# hand_bot.net
KiCad netlist of a schematic drawn in Altium Designer
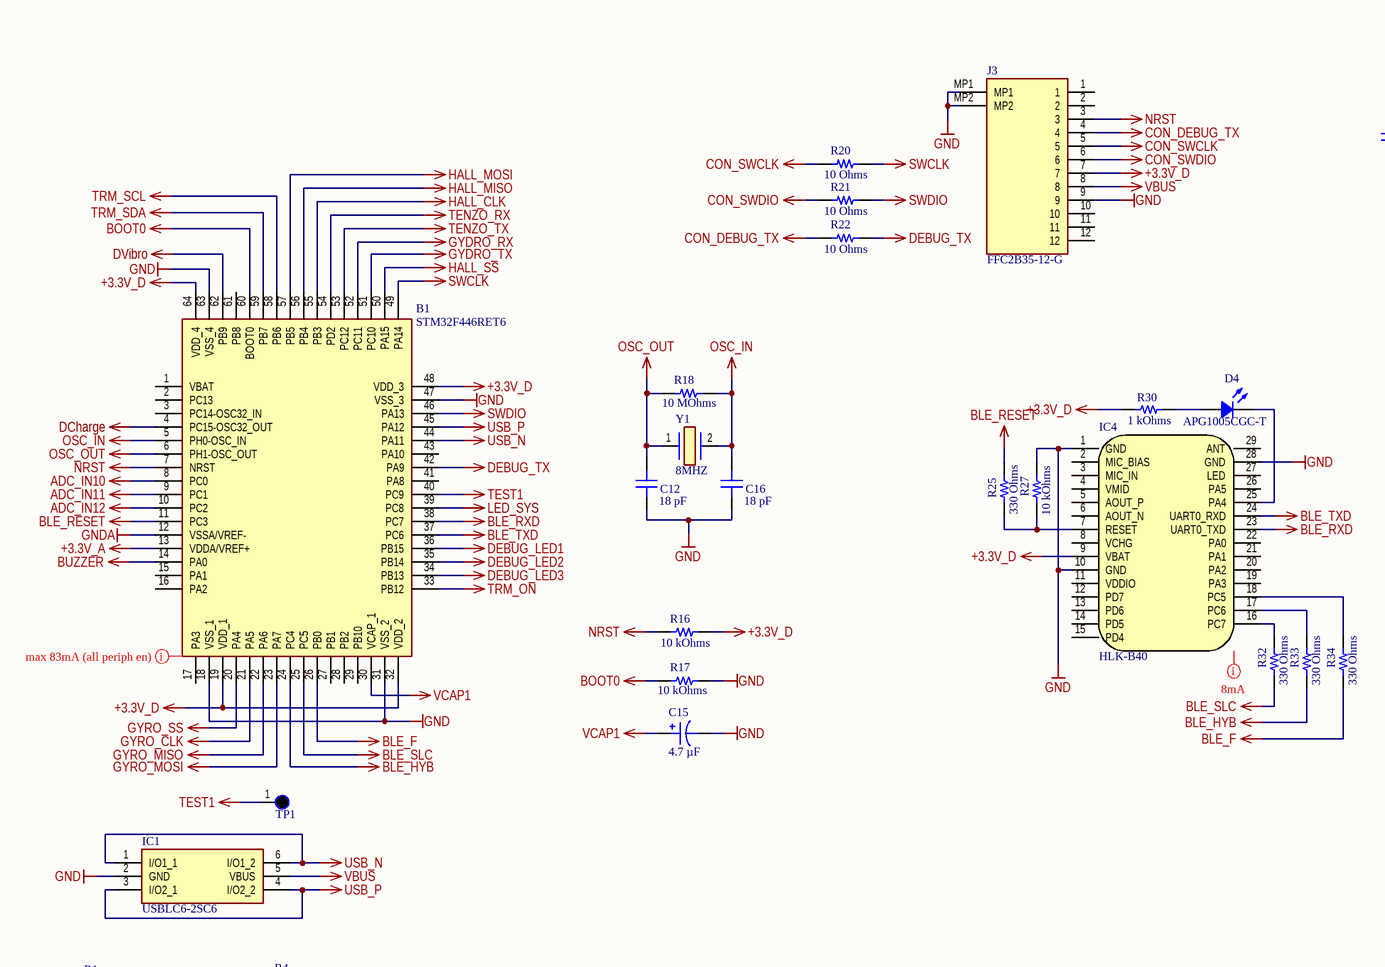
[diagram p0: hand_bot.SchDoc, top left]
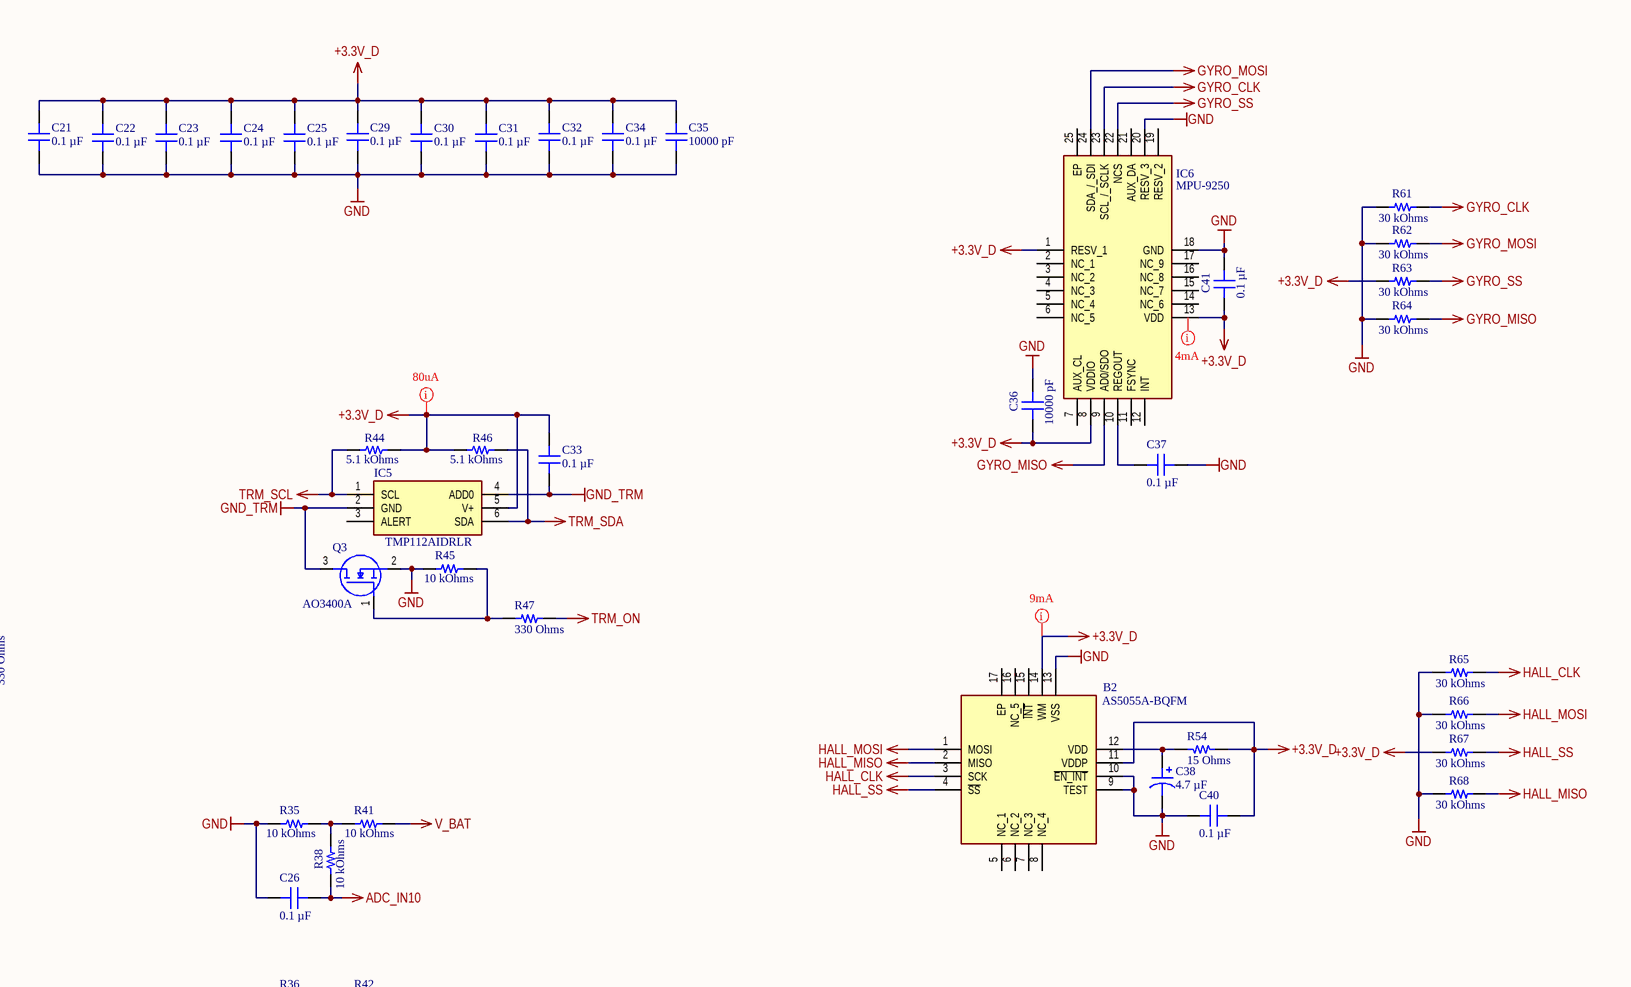
[diagram p1: hand_bot.SchDoc, top right]
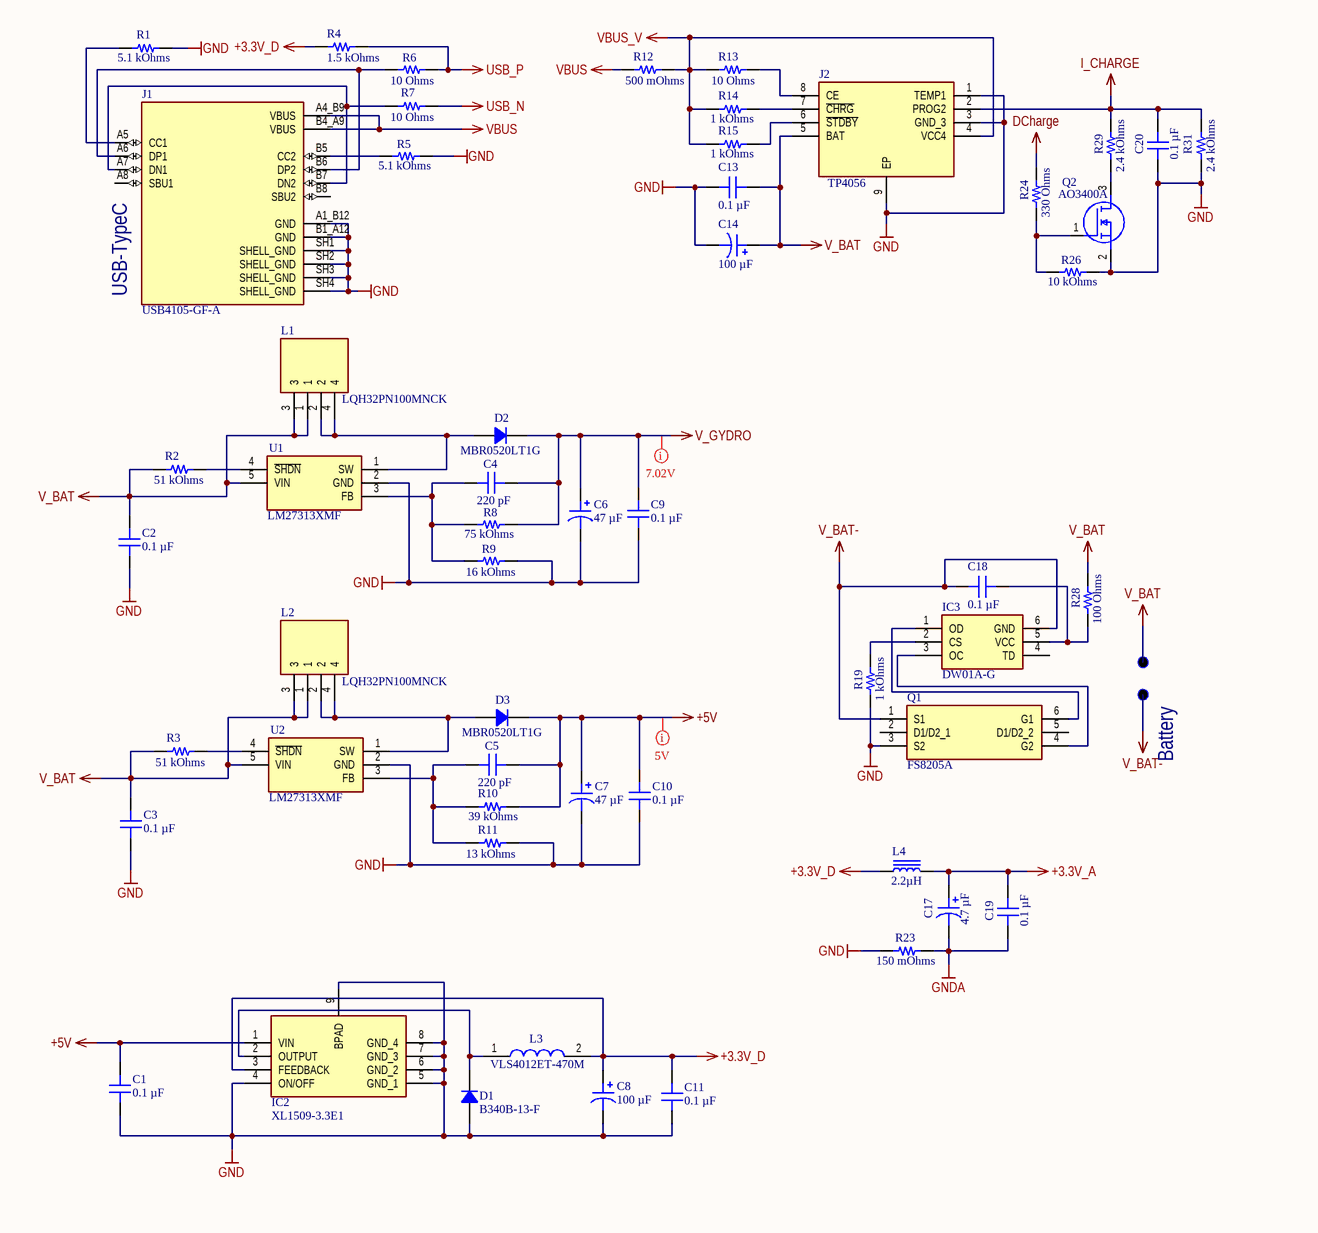
[diagram p2: hand_bot.SchDoc, bottom left]
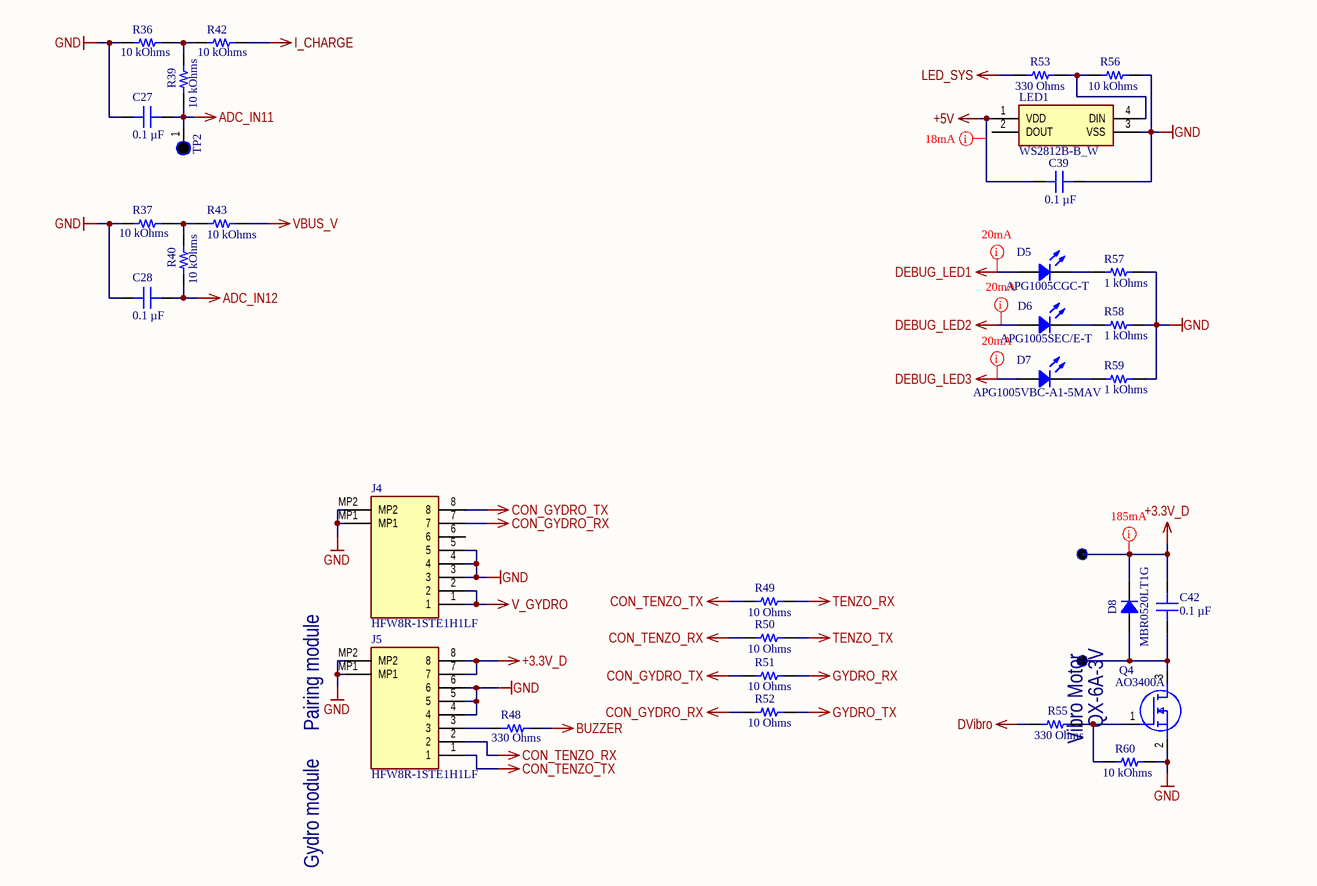
[diagram p3: hand_bot.SchDoc, bottom right]

(export (version "E")
  (design (tool "Eeschema 10.0.6"))
  (components
    (comp (ref "B1")
      (value "STM32F446RET6")
      (footprint "SamacSys:QFP50P1200X1200X160-64N")
      (description "Integrated Circuit")
      (fields (field (name "MOUSER PART NUMBER") "511-STM32F446RET6"))
      (libsource (lib "*") (part "STM32F446RET6"))
    )
    (comp (ref "B2")
      (value "AS5055A-BQFM")
      (footprint "SamacSys:QFN65P400X400X100-17N-D")
      (description "Integrated Circuit")
      (fields (field (name "MOUSER PART NUMBER") "985-AS5055A-BQFM"))
      (libsource (lib "SamacSys") (part "AS5055A-BQFM"))
    )
    (comp (ref "C1")
      (value "0.1 µF")
      (footprint "CAP 0402_1005")
      (description "CAP CER 0.1UF 50V X7R 0402")
      (fields (field (name "PART NUMBER") "CC0402KRX7R9BB104") (field (name "MANUFACTURER") "Yageo"))
      (libsource (lib "Celestial Altium Library - altium_library") (part "Capacitor"))
    )
    (comp (ref "C2")
      (value "0.1 µF")
      (footprint "CAP 0402_1005")
      (description "CAP CER 0.1UF 50V X7R 0402")
      (fields (field (name "PART NUMBER") "CC0402KRX7R9BB104") (field (name "MANUFACTURER") "Yageo"))
      (libsource (lib "Celestial Altium Library - altium_library") (part "Capacitor"))
    )
    (comp (ref "C3")
      (value "0.1 µF")
      (footprint "CAP 0402_1005")
      (description "CAP CER 0.1UF 50V X7R 0402")
      (fields (field (name "PART NUMBER") "CC0402KRX7R9BB104") (field (name "MANUFACTURER") "Yageo"))
      (libsource (lib "Celestial Altium Library - altium_library") (part "Capacitor"))
    )
    (comp (ref "C4")
      (value "220 pF")
      (footprint "CAP 0402_1005")
      (description "CAP CER 220PF 50V X7R 0402")
      (fields (field (name "PART NUMBER") "CC0402JRX7R9BB221") (field (name "MANUFACTURER") "Yageo"))
      (libsource (lib "Celestial Altium Library - altium_library") (part "Capacitor"))
    )
    (comp (ref "C5")
      (value "220 pF")
      (footprint "CAP 0402_1005")
      (description "CAP CER 220PF 50V X7R 0402")
      (fields (field (name "PART NUMBER") "CC0402JRX7R9BB221") (field (name "MANUFACTURER") "Yageo"))
      (libsource (lib "Celestial Altium Library - altium_library") (part "Capacitor"))
    )
    (comp (ref "C6")
      (value "47 µF")
      (footprint "CAP POL 1411_3528")
      (description "CAP TANT 47UF 20% 16V 1411")
      (fields (field (name "PART NUMBER") "TMCMB1C476MTRF") (field (name "MANUFACTURER") "Vishay Sprague"))
      (libsource (lib "Celestial Altium Library - altium_library") (part "Polarised Capacitor"))
    )
    (comp (ref "C7")
      (value "47 µF")
      (footprint "CAP POL 1411_3528")
      (description "CAP TANT 47UF 20% 16V 1411")
      (fields (field (name "PART NUMBER") "TMCMB1C476MTRF") (field (name "MANUFACTURER") "Vishay Sprague"))
      (libsource (lib "Celestial Altium Library - altium_library") (part "Polarised Capacitor"))
    )
    (comp (ref "C8")
      (value "100 µF")
      (footprint "CAP POL 1411_3528")
      (description "CAP TANT 100UF 20% 10V 1411")
      (fields (field (name "PART NUMBER") "T495B107M010ATE500") (field (name "MANUFACTURER") "KEMET"))
      (libsource (lib "Celestial Altium Library - altium_library") (part "Polarised Capacitor"))
    )
    (comp (ref "C9")
      (value "0.1 µF")
      (footprint "CAP 0402_1005")
      (description "CAP CER 0.1UF 50V X7R 0402")
      (fields (field (name "PART NUMBER") "CC0402KRX7R9BB104") (field (name "MANUFACTURER") "Yageo"))
      (libsource (lib "Celestial Altium Library - altium_library") (part "Capacitor"))
    )
    (comp (ref "C10")
      (value "0.1 µF")
      (footprint "CAP 0402_1005")
      (description "CAP CER 0.1UF 50V X7R 0402")
      (fields (field (name "PART NUMBER") "CC0402KRX7R9BB104") (field (name "MANUFACTURER") "Yageo"))
      (libsource (lib "Celestial Altium Library - altium_library") (part "Capacitor"))
    )
    (comp (ref "C11")
      (value "0.1 µF")
      (footprint "CAP 0402_1005")
      (description "CAP CER 0.1UF 50V X7R 0402")
      (fields (field (name "PART NUMBER") "CC0402KRX7R9BB104") (field (name "MANUFACTURER") "Yageo"))
      (libsource (lib "Celestial Altium Library - altium_library") (part "Capacitor"))
    )
    (comp (ref "C12")
      (value "18 pF")
      (footprint "CAP 0402_1005")
      (description "CAP CER 18PF 50V C0G/NPO 0402")
      (fields (field (name "PART NUMBER") "CC0402FRNPO9BN180") (field (name "MANUFACTURER") "Yageo"))
      (libsource (lib "Celestial Altium Library - altium_library") (part "Capacitor"))
    )
    (comp (ref "C13")
      (value "0.1 µF")
      (footprint "CAP 0402_1005")
      (description "CAP CER 0.1UF 50V X7R 0402")
      (fields (field (name "PART NUMBER") "CC0402KRX7R9BB104") (field (name "MANUFACTURER") "Yageo"))
      (libsource (lib "Celestial Altium Library - altium_library") (part "Capacitor"))
    )
    (comp (ref "C14")
      (value "100 µF")
      (footprint "CAP POL 1411_3528")
      (description "CAP TANT 100UF 20% 10V 1411")
      (fields (field (name "PART NUMBER") "T495B107M010ATE500") (field (name "MANUFACTURER") "KEMET"))
      (libsource (lib "") (part "Polarised Capacitor_1"))
    )
    (comp (ref "C15")
      (value "4.7 µF")
      (footprint "CAP POL 1206_3216")
      (description "CAP TANT 4.7UF 20% 16V 1206")
      (fields (field (name "PART NUMBER") "T491A475M016AT") (field (name "MANUFACTURER") "KEMET"))
      (libsource (lib "") (part "Polarised Capacitor_1"))
    )
    (comp (ref "C16")
      (value "18 pF")
      (footprint "CAP 0402_1005")
      (description "CAP CER 18PF 50V C0G/NPO 0402")
      (fields (field (name "PART NUMBER") "CC0402FRNPO9BN180") (field (name "MANUFACTURER") "Yageo"))
      (libsource (lib "Celestial Altium Library - altium_library") (part "Capacitor"))
    )
    (comp (ref "C17")
      (value "4.7 µF")
      (footprint "CAP POL 1206_3216")
      (description "CAP TANT 4.7UF 20% 16V 1206")
      (fields (field (name "PART NUMBER") "T491A475M016AT") (field (name "MANUFACTURER") "KEMET"))
      (libsource (lib "Celestial Altium Library - altium_library") (part "Polarised Capacitor"))
    )
    (comp (ref "C18")
      (value "0.1 µF")
      (footprint "CAP 0402_1005")
      (description "CAP CER 0.1UF 50V X7R 0402")
      (fields (field (name "PART NUMBER") "CC0402KRX7R9BB104") (field (name "MANUFACTURER") "Yageo"))
      (libsource (lib "Celestial Altium Library - altium_library") (part "Capacitor"))
    )
    (comp (ref "C19")
      (value "0.1 µF")
      (footprint "CAP 0402_1005")
      (description "CAP CER 0.1UF 50V X7R 0402")
      (fields (field (name "PART NUMBER") "CC0402KRX7R9BB104") (field (name "MANUFACTURER") "Yageo"))
      (libsource (lib "Celestial Altium Library - altium_library") (part "Capacitor"))
    )
    (comp (ref "C20")
      (value "0.1 µF")
      (footprint "CAP 0402_1005")
      (description "CAP CER 0.1UF 50V X7R 0402")
      (fields (field (name "PART NUMBER") "CC0402KRX7R9BB104") (field (name "MANUFACTURER") "Yageo"))
      (libsource (lib "Celestial Altium Library - altium_library") (part "Capacitor"))
    )
    (comp (ref "C21")
      (value "0.1 µF")
      (footprint "CAP 0402_1005")
      (description "CAP CER 0.1UF 50V X7R 0402")
      (fields (field (name "PART NUMBER") "CC0402KRX7R9BB104") (field (name "MANUFACTURER") "Yageo"))
      (libsource (lib "Celestial Altium Library - altium_library") (part "Capacitor"))
    )
    (comp (ref "C22")
      (value "0.1 µF")
      (footprint "CAP 0402_1005")
      (description "CAP CER 0.1UF 50V X7R 0402")
      (fields (field (name "PART NUMBER") "CC0402KRX7R9BB104") (field (name "MANUFACTURER") "Yageo"))
      (libsource (lib "Celestial Altium Library - altium_library") (part "Capacitor"))
    )
    (comp (ref "C23")
      (value "0.1 µF")
      (footprint "CAP 0402_1005")
      (description "CAP CER 0.1UF 50V X7R 0402")
      (fields (field (name "PART NUMBER") "CC0402KRX7R9BB104") (field (name "MANUFACTURER") "Yageo"))
      (libsource (lib "Celestial Altium Library - altium_library") (part "Capacitor"))
    )
    (comp (ref "C24")
      (value "0.1 µF")
      (footprint "CAP 0402_1005")
      (description "CAP CER 0.1UF 50V X7R 0402")
      (fields (field (name "PART NUMBER") "CC0402KRX7R9BB104") (field (name "MANUFACTURER") "Yageo"))
      (libsource (lib "Celestial Altium Library - altium_library") (part "Capacitor"))
    )
    (comp (ref "C25")
      (value "0.1 µF")
      (footprint "CAP 0402_1005")
      (description "CAP CER 0.1UF 50V X7R 0402")
      (fields (field (name "PART NUMBER") "CC0402KRX7R9BB104") (field (name "MANUFACTURER") "Yageo"))
      (libsource (lib "Celestial Altium Library - altium_library") (part "Capacitor"))
    )
    (comp (ref "C26")
      (value "0.1 µF")
      (footprint "CAP 0402_1005")
      (description "CAP CER 0.1UF 50V X7R 0402")
      (fields (field (name "PART NUMBER") "CC0402KRX7R9BB104") (field (name "MANUFACTURER") "Yageo"))
      (libsource (lib "Celestial Altium Library - altium_library") (part "Capacitor"))
    )
    (comp (ref "C27")
      (value "0.1 µF")
      (footprint "CAP 0402_1005")
      (description "CAP CER 0.1UF 50V X7R 0402")
      (fields (field (name "PART NUMBER") "CC0402KRX7R9BB104") (field (name "MANUFACTURER") "Yageo"))
      (libsource (lib "Celestial Altium Library - altium_library") (part "Capacitor"))
    )
    (comp (ref "C28")
      (value "0.1 µF")
      (footprint "CAP 0402_1005")
      (description "CAP CER 0.1UF 50V X7R 0402")
      (fields (field (name "PART NUMBER") "CC0402KRX7R9BB104") (field (name "MANUFACTURER") "Yageo"))
      (libsource (lib "Celestial Altium Library - altium_library") (part "Capacitor"))
    )
    (comp (ref "C29")
      (value "0.1 µF")
      (footprint "CAP 0402_1005")
      (description "CAP CER 0.1UF 50V X7R 0402")
      (fields (field (name "PART NUMBER") "CC0402KRX7R9BB104") (field (name "MANUFACTURER") "Yageo"))
      (libsource (lib "Celestial Altium Library - altium_library") (part "Capacitor"))
    )
    (comp (ref "C30")
      (value "0.1 µF")
      (footprint "CAP 0402_1005")
      (description "CAP CER 0.1UF 50V X7R 0402")
      (fields (field (name "PART NUMBER") "CC0402KRX7R9BB104") (field (name "MANUFACTURER") "Yageo"))
      (libsource (lib "Celestial Altium Library - altium_library") (part "Capacitor"))
    )
    (comp (ref "C31")
      (value "0.1 µF")
      (footprint "CAP 0402_1005")
      (description "CAP CER 0.1UF 50V X7R 0402")
      (fields (field (name "PART NUMBER") "CC0402KRX7R9BB104") (field (name "MANUFACTURER") "Yageo"))
      (libsource (lib "Celestial Altium Library - altium_library") (part "Capacitor"))
    )
    (comp (ref "C32")
      (value "0.1 µF")
      (footprint "CAP 0402_1005")
      (description "CAP CER 0.1UF 50V X7R 0402")
      (fields (field (name "PART NUMBER") "CC0402KRX7R9BB104") (field (name "MANUFACTURER") "Yageo"))
      (libsource (lib "Celestial Altium Library - altium_library") (part "Capacitor"))
    )
    (comp (ref "C33")
      (value "0.1 µF")
      (footprint "CAP 0402_1005")
      (description "CAP CER 0.1UF 50V X7R 0402")
      (fields (field (name "PART NUMBER") "CC0402KRX7R9BB104") (field (name "MANUFACTURER") "Yageo"))
      (libsource (lib "Celestial Altium Library - altium_library") (part "Capacitor"))
    )
    (comp (ref "C34")
      (value "0.1 µF")
      (footprint "CAP 0402_1005")
      (description "CAP CER 0.1UF 50V X7R 0402")
      (fields (field (name "PART NUMBER") "CC0402KRX7R9BB104") (field (name "MANUFACTURER") "Yageo"))
      (libsource (lib "Celestial Altium Library - altium_library") (part "Capacitor"))
    )
    (comp (ref "C35")
      (value "10000 pF")
      (footprint "CAP 0402_1005")
      (description "CAP CER 10000PF 50V X7R 0402")
      (fields (field (name "PART NUMBER") "CC0402KRX7R9BB103") (field (name "MANUFACTURER") "Yageo"))
      (libsource (lib "Celestial Altium Library - altium_library") (part "Capacitor"))
    )
    (comp (ref "C36")
      (value "10000 pF")
      (footprint "CAP 0402_1005")
      (description "CAP CER 10000PF 50V X7R 0402")
      (fields (field (name "PART NUMBER") "CC0402KRX7R9BB103") (field (name "MANUFACTURER") "Yageo"))
      (libsource (lib "Celestial Altium Library - altium_library") (part "Capacitor"))
    )
    (comp (ref "C37")
      (value "0.1 µF")
      (footprint "CAP 0402_1005")
      (description "CAP CER 0.1UF 50V X7R 0402")
      (fields (field (name "PART NUMBER") "CC0402KRX7R9BB104") (field (name "MANUFACTURER") "Yageo"))
      (libsource (lib "Celestial Altium Library - altium_library") (part "Capacitor"))
    )
    (comp (ref "C38")
      (value "4.7 µF")
      (footprint "CAP POL 1206_3216")
      (description "CAP TANT 4.7UF 20% 16V 1206")
      (fields (field (name "PART NUMBER") "T491A475M016AT") (field (name "MANUFACTURER") "KEMET"))
      (libsource (lib "Celestial Altium Library - altium_library") (part "Polarised Capacitor"))
    )
    (comp (ref "C39")
      (value "0.1 µF")
      (footprint "CAP 0402_1005")
      (description "CAP CER 0.1UF 50V X7R 0402")
      (fields (field (name "PART NUMBER") "CC0402KRX7R9BB104") (field (name "MANUFACTURER") "Yageo"))
      (libsource (lib "Celestial Altium Library - altium_library") (part "Capacitor"))
    )
    (comp (ref "C40")
      (value "0.1 µF")
      (footprint "CAP 0402_1005")
      (description "CAP CER 0.1UF 50V X7R 0402")
      (fields (field (name "PART NUMBER") "CC0402KRX7R9BB104") (field (name "MANUFACTURER") "Yageo"))
      (libsource (lib "Celestial Altium Library - altium_library") (part "Capacitor"))
    )
    (comp (ref "C41")
      (value "0.1 µF")
      (footprint "CAP 0402_1005")
      (description "CAP CER 0.1UF 50V X7R 0402")
      (fields (field (name "PART NUMBER") "CC0402KRX7R9BB104") (field (name "MANUFACTURER") "Yageo"))
      (libsource (lib "Celestial Altium Library - altium_library") (part "Capacitor"))
    )
    (comp (ref "C42")
      (value "0.1 µF")
      (footprint "CAP 0402_1005")
      (description "CAP CER 0.1UF 50V X7R 0402")
      (fields (field (name "PART NUMBER") "CC0402KRX7R9BB104") (field (name "MANUFACTURER") "Yageo"))
      (libsource (lib "Celestial Altium Library - altium_library") (part "Capacitor"))
    )
    (comp (ref "D1")
      (value "B340B-13-F")
      (footprint "DO214AA SMB")
      (description "DIODE SCHOTTKY 40V 3A SMB")
      (fields (field (name "MANUFACTURER") "Diodes Incorporated"))
      (libsource (lib "Celestial Altium Library - altium_library") (part "Diode"))
    )
    (comp (ref "D2")
      (value "MBR0520LT1G")
      (footprint "SOD-123")
      (description "DIODE SCHOTTKY 20V 500MA SOD123")
      (fields (field (name "MANUFACTURER") "ON Semiconductor"))
      (libsource (lib "Celestial Altium Library - altium_library") (part "Diode"))
    )
    (comp (ref "D3")
      (value "MBR0520LT1G")
      (footprint "SOD-123")
      (description "DIODE SCHOTTKY 20V 500MA SOD123")
      (fields (field (name "MANUFACTURER") "ON Semiconductor"))
      (libsource (lib "Celestial Altium Library - altium_library") (part "Diode"))
    )
    (comp (ref "D4")
      (value "APG1005CGC-T")
      (footprint "LED 0402_1005 GREEN")
      (description "LED GREEN CLEAR CHIP SMD")
      (fields (field (name "MANUFACTURER") "Kingbright"))
      (libsource (lib "Celestial Altium Library - altium_library") (part "LED"))
    )
    (comp (ref "D5")
      (value "APG1005CGC-T")
      (footprint "LED 0402_1005 GREEN")
      (description "LED GREEN CLEAR CHIP SMD")
      (fields (field (name "MANUFACTURER") "Kingbright"))
      (libsource (lib "Celestial Altium Library - altium_library") (part "LED"))
    )
    (comp (ref "D6")
      (value "Red")
      (footprint "LED 0402_1005 RED")
      (description "LED RED CLEAR CHIP SMD")
      (fields (field (name "PART NUMBER") "APG1005SEC/E-T") (field (name "MANUFACTURER") "Kingbright"))
      (libsource (lib "Celestial Altium Library - altium_library") (part "LED"))
    )
    (comp (ref "D7")
      (value "Blue")
      (footprint "LED 0402_1005 BLUE")
      (description "LED BLUE CLEAR 0402 SMD")
      (fields (field (name "PART NUMBER") "APG1005VBC-A1-5MAV") (field (name "MANUFACTURER") "Kingbright"))
      (libsource (lib "Celestial Altium Library - altium_library") (part "LED"))
    )
    (comp (ref "D8")
      (value "MBR0520LT1G")
      (footprint "SOD-123")
      (description "DIODE SCHOTTKY 20V 500MA SOD123")
      (fields (field (name "MANUFACTURER") "ON Semiconductor"))
      (libsource (lib "Celestial Altium Library - altium_library") (part "Diode"))
    )
    (comp (ref "IC1")
      (value "USBLC6-2SC6")
      (footprint "SamacSys:SOT95P280X145-6N")
      (description "Integrated Circuit")
      (fields (field (name "MOUSER PART NUMBER") "511-USBLC6-2SC6"))
      (libsource (lib "*") (part "USBLC6-2SC6"))
    )
    (comp (ref "IC2")
      (value "XL1509-3.3E1")
      (footprint "SamacSys:SOIC127P600X175-8N_BPAD")
      (description "Integrated Circuit")
      (libsource (lib "SamacSys") (part "XL1509-3.3E1"))
    )
    (comp (ref "IC3")
      (value "DW01A-G")
      (footprint "SamacSys:SOT95P280X135-6N")
      (description "Integrated Circuit")
      (libsource (lib "*") (part "DW01A-G"))
    )
    (comp (ref "IC4")
      (value "HLK-B40")
      (footprint "hlk-b40")
      (fields (field (name "MANUFACTURER") "HI-LINK(海凌科)"))
      (libsource (lib "SamacSys") (part "HLK-B40"))
    )
    (comp (ref "IC5")
      (value "TMP112AIDRLR")
      (footprint "SamacSys:SOTFL50P160X60-6N")
      (description "Integrated Circuit")
      (fields (field (name "MANUFACTURER_PART_NUMBER") "TMP112AIDRLR-869127202"))
      (libsource (lib "*") (part "TMP112AIDRLR-869127202"))
    )
    (comp (ref "IC6")
      (value "MPU-9250")
      (footprint "SamacSys:QFN40P300X300X105-25N-D")
      (description "Integrated Circuit")
      (fields (field (name "MANUFACTURER_PART_NUMBER") "InvenSense MPU-9250"))
      (libsource (lib "*") (part "InvenSense_MPU-9250"))
    )
    (comp (ref "J1")
      (value "USB4105-GF-A")
      (footprint "GCT_USB4105-GF-A")
      (fields (field (name "MF") "GCT"))
      (libsource (lib "USB4105-GF-A") (part "USB4105-GF-A"))
    )
    (comp (ref "J2")
      (value "TP4056")
      (footprint "SamacSys:SOIC127P600X175-9N")
      (description "Connector")
      (libsource (lib "*") (part "TP4056"))
    )
    (comp (ref "J3")
      (value "FFC2B35-12-G")
      (footprint "SamacSys:FFC2B3512G")
      (description "Connector")
      (fields (field (name "MOUSER PART NUMBER") "640-FFC2B35-12-G"))
      (libsource (lib "*") (part "FFC2B35-12-G"))
    )
    (comp (ref "J4")
      (value "HFW8R-1STE1H1LF")
      (footprint "SamacSys:HFW8R1STE1H1LF")
      (description "Connector")
      (fields (field (name "MOUSER PART NUMBER") "649-HFW8R-1STE1H1LF"))
      (libsource (lib "SamacSys") (part "HFW8R-1STE1H1LF"))
    )
    (comp (ref "J5")
      (value "HFW8R-1STE1H1LF")
      (footprint "SamacSys:HFW8R1STE1H1LF")
      (description "Connector")
      (fields (field (name "MOUSER PART NUMBER") "649-HFW8R-1STE1H1LF"))
      (libsource (lib "SamacSys") (part "HFW8R-1STE1H1LF"))
    )
    (comp (ref "L1")
      (value "LQH32PN100MNCK")
      (footprint "SamacSys:LQH32CH100K53L")
      (description "Inductor")
      (libsource (lib "*") (part "LQH32PN100MNCK"))
    )
    (comp (ref "L2")
      (value "LQH32PN100MNCK")
      (footprint "SamacSys:LQH32CH100K53L")
      (description "Inductor")
      (libsource (lib "*") (part "LQH32PN100MNCK"))
    )
    (comp (ref "L3")
      (value "VLS4012ET-470M")
      (footprint "SamacSys:VLS4012")
      (description "Inductor")
      (fields (field (name "MOUSER PART NUMBER") "810-VLS4012ET-470M"))
      (libsource (lib "*") (part "VLS4012ET-470M"))
    )
    (comp (ref "L4")
      (value "2.2µH")
      (footprint "IND 0603_1608 RF WW")
      (description "FIXED IND 2.2UH 750MA 345 MOHM")
      (fields (field (name "PART NUMBER") "MBKK1608T2R2M") (field (name "MANUFACTURER") "Taiyo Yuden"))
      (libsource (lib "Celestial Altium Library - altium_library") (part "Inductor"))
    )
    (comp (ref "LED1")
      (value "WS2812B-B_W")
      (footprint "SamacSys:WS2812BBW")
      (description "LED")
      (fields (field (name "MANUFACTURER_PART_NUMBER") "WS2812B-B/W"))
      (libsource (lib "*") (part "WS2812B-B_W"))
    )
    (comp (ref "Q1")
      (value "FS8205A")
      (footprint "SamacSys:SOT95P280X125-6N")
      (description "MOSFET (N-Channel)")
      (libsource (lib "*") (part "FS8205A"))
    )
    (comp (ref "Q2")
      (value "AO3400A")
      (footprint "SamacSys:SOT95P280X125-3N")
      (description "MOSFET (N-Channel)")
      (libsource (lib "SamacSys") (part "AO3400A"))
    )
    (comp (ref "Q3")
      (value "AO3400A")
      (footprint "SamacSys:SOT95P280X125-3N")
      (description "MOSFET (N-Channel)")
      (libsource (lib "SamacSys") (part "AO3400A"))
    )
    (comp (ref "Q4")
      (value "AO3400A")
      (footprint "SamacSys:SOT95P280X125-3N")
      (description "MOSFET (N-Channel)")
      (libsource (lib "SamacSys") (part "AO3400A"))
    )
    (comp (ref "R1")
      (value "5.1 kOhms")
      (footprint "RES 0402_1005")
      (description "RES 5.1K OHM 1% 1/16W 0402")
      (fields
        (field (name "PART NUMBER") "RMCF0402FT5K10")
        (field (name "MANUFACTURER") "Stackpole Electronics Inc")
      )
      (libsource (lib "Celestial Altium Library - altium_library") (part "Resistor"))
    )
    (comp (ref "R2")
      (value "51 kOhms")
      (footprint "RES 0402_1005")
      (description "RES 51K OHM 1% 1/16W 0402")
      (fields (field (name "PART NUMBER") "RC0402FR-0751KL") (field (name "MANUFACTURER") "Yageo"))
      (libsource (lib "Celestial Altium Library - altium_library") (part "Resistor"))
    )
    (comp (ref "R3")
      (value "51 kOhms")
      (footprint "RES 0402_1005")
      (description "RES 51K OHM 1% 1/16W 0402")
      (fields (field (name "PART NUMBER") "RC0402FR-0751KL") (field (name "MANUFACTURER") "Yageo"))
      (libsource (lib "Celestial Altium Library - altium_library") (part "Resistor"))
    )
    (comp (ref "R4")
      (value "1.5 kOhms")
      (footprint "RES 0402_1005")
      (description "RES 1.5K OHM 1% 1/16W 0402")
      (fields (field (name "PART NUMBER") "RC0402FR-071K5L") (field (name "MANUFACTURER") "Yageo"))
      (libsource (lib "Celestial Altium Library - altium_library") (part "Resistor"))
    )
    (comp (ref "R5")
      (value "5.1 kOhms")
      (footprint "RES 0402_1005")
      (description "RES 5.1K OHM 1% 1/16W 0402")
      (fields
        (field (name "PART NUMBER") "RMCF0402FT5K10")
        (field (name "MANUFACTURER") "Stackpole Electronics Inc")
      )
      (libsource (lib "Celestial Altium Library - altium_library") (part "Resistor"))
    )
    (comp (ref "R6")
      (value "10 Ohms")
      (footprint "RES 0402_1005")
      (description "RES 10 OHM 1% 1/8W 0402")
      (fields (field (name "PART NUMBER") "RC0402FR-7W10RL") (field (name "MANUFACTURER") "Yageo"))
      (libsource (lib "Celestial Altium Library - altium_library") (part "Resistor"))
    )
    (comp (ref "R7")
      (value "10 Ohms")
      (footprint "RES 0402_1005")
      (description "RES 10 OHM 1% 1/8W 0402")
      (fields (field (name "PART NUMBER") "RC0402FR-7W10RL") (field (name "MANUFACTURER") "Yageo"))
      (libsource (lib "Celestial Altium Library - altium_library") (part "Resistor"))
    )
    (comp (ref "R8")
      (value "75 kOhms")
      (footprint "RES 0402_1005")
      (description "RES 75K OHM 1% 1/16W 0402")
      (fields (field (name "PART NUMBER") "RC0402FR-0775KL") (field (name "MANUFACTURER") "Yageo"))
      (libsource (lib "Celestial Altium Library - altium_library") (part "Resistor"))
    )
    (comp (ref "R9")
      (value "16 kOhms")
      (footprint "RES 0402_1005")
      (description "RES 16K OHM 1% 1/16W 0402")
      (fields (field (name "PART NUMBER") "RC0402FR-0716KL") (field (name "MANUFACTURER") "Yageo"))
      (libsource (lib "Celestial Altium Library - altium_library") (part "Resistor"))
    )
    (comp (ref "R10")
      (value "39 kOhms")
      (footprint "RES 0402_1005")
      (description "RES 39K OHM 1% 1/16W 0402")
      (fields (field (name "PART NUMBER") "RC0402FR-0739KL") (field (name "MANUFACTURER") "Yageo"))
      (libsource (lib "Celestial Altium Library - altium_library") (part "Resistor"))
    )
    (comp (ref "R11")
      (value "13 kOhms")
      (footprint "RES 0402_1005")
      (description "RES 13K OHM 1% 1/16W 0402")
      (fields (field (name "PART NUMBER") "RC0402FR-0713KL") (field (name "MANUFACTURER") "Yageo"))
      (libsource (lib "Celestial Altium Library - altium_library") (part "Resistor"))
    )
    (comp (ref "R12")
      (value "500 mOhms")
      (footprint "RES 2512_6432")
      (description "RES 0.5 OHM 1% 1W 2512")
      (fields (field (name "PART NUMBER") "RL2512FK-070R5L") (field (name "MANUFACTURER") "Yageo"))
      (libsource (lib "Celestial Altium Library - altium_library") (part "Resistor"))
    )
    (comp (ref "R13")
      (value "10 Ohms")
      (footprint "RES 0402_1005")
      (description "RES 10 OHM 1% 1/8W 0402")
      (fields (field (name "PART NUMBER") "RC0402FR-7W10RL") (field (name "MANUFACTURER") "Yageo"))
      (libsource (lib "Celestial Altium Library - altium_library") (part "Resistor"))
    )
    (comp (ref "R14")
      (value "1 kOhms")
      (footprint "RES 0402_1005")
      (description "RES SMD 1K OHM 1% 1/16W 0402")
      (fields (field (name "PART NUMBER") "CR0402-FX-1001GLF") (field (name "MANUFACTURER") "Bourns Inc."))
      (libsource (lib "Celestial Altium Library - altium_library") (part "Resistor"))
    )
    (comp (ref "R15")
      (value "1 kOhms")
      (footprint "RES 0402_1005")
      (description "RES SMD 1K OHM 1% 1/16W 0402")
      (fields (field (name "PART NUMBER") "CR0402-FX-1001GLF") (field (name "MANUFACTURER") "Bourns Inc."))
      (libsource (lib "Celestial Altium Library - altium_library") (part "Resistor"))
    )
    (comp (ref "R16")
      (value "10 kOhms")
      (footprint "RES 0402_1005")
      (description "RES 10K OHM 1% 1/16W 0402")
      (fields
        (field (name "PART NUMBER") "RMCF0402FT10K0")
        (field (name "MANUFACTURER") "Stackpole Electronics Inc")
      )
      (libsource (lib "Celestial Altium Library - altium_library") (part "Resistor"))
    )
    (comp (ref "R17")
      (value "10 kOhms")
      (footprint "RES 0402_1005")
      (description "RES 10K OHM 1% 1/16W 0402")
      (fields
        (field (name "PART NUMBER") "RMCF0402FT10K0")
        (field (name "MANUFACTURER") "Stackpole Electronics Inc")
      )
      (libsource (lib "Celestial Altium Library - altium_library") (part "Resistor"))
    )
    (comp (ref "R18")
      (value "10 MOhms")
      (footprint "RES 0402_1005")
      (description "RES 10M OHM 1% 1/16W 0402")
      (fields (field (name "PART NUMBER") "RC0402FR-0710ML") (field (name "MANUFACTURER") "Yageo"))
      (libsource (lib "Celestial Altium Library - altium_library") (part "Resistor"))
    )
    (comp (ref "R19")
      (value "1 kOhms")
      (footprint "RES 0402_1005")
      (description "RES SMD 1K OHM 1% 1/16W 0402")
      (fields (field (name "PART NUMBER") "CR0402-FX-1001GLF") (field (name "MANUFACTURER") "Bourns Inc."))
      (libsource (lib "Celestial Altium Library - altium_library") (part "Resistor"))
    )
    (comp (ref "R20")
      (value "10 Ohms")
      (footprint "RES 0402_1005")
      (description "RES 10 OHM 1% 1/8W 0402")
      (fields (field (name "PART NUMBER") "RC0402FR-7W10RL") (field (name "MANUFACTURER") "Yageo"))
      (libsource (lib "Celestial Altium Library - altium_library") (part "Resistor"))
    )
    (comp (ref "R21")
      (value "10 Ohms")
      (footprint "RES 0402_1005")
      (description "RES 10 OHM 1% 1/8W 0402")
      (fields (field (name "PART NUMBER") "RC0402FR-7W10RL") (field (name "MANUFACTURER") "Yageo"))
      (libsource (lib "Celestial Altium Library - altium_library") (part "Resistor"))
    )
    (comp (ref "R22")
      (value "10 Ohms")
      (footprint "RES 0402_1005")
      (description "RES 10 OHM 1% 1/8W 0402")
      (fields (field (name "PART NUMBER") "RC0402FR-7W10RL") (field (name "MANUFACTURER") "Yageo"))
      (libsource (lib "Celestial Altium Library - altium_library") (part "Resistor"))
    )
    (comp (ref "R23")
      (value "150 mOhms")
      (footprint "RES 0805_2012")
      (description "RES 0.15 OHM 1% 1/8W 0805")
      (fields (field (name "PART NUMBER") "RL0805FR-070R15L") (field (name "MANUFACTURER") "Yageo"))
      (libsource (lib "Celestial Altium Library - altium_library") (part "Resistor"))
    )
    (comp (ref "R24")
      (value "330 Ohms")
      (footprint "RES 0402_1005")
      (description "RES 330 OHM 1% 1/16W 0402")
      (fields
        (field (name "PART NUMBER") "RMCF0402FT330R")
        (field (name "MANUFACTURER") "Stackpole Electronics Inc")
      )
      (libsource (lib "Celestial Altium Library - altium_library") (part "Resistor"))
    )
    (comp (ref "R25")
      (value "330 Ohms")
      (footprint "RES 0402_1005")
      (description "RES 330 OHM 1% 1/16W 0402")
      (fields
        (field (name "PART NUMBER") "RMCF0402FT330R")
        (field (name "MANUFACTURER") "Stackpole Electronics Inc")
      )
      (libsource (lib "Celestial Altium Library - altium_library") (part "Resistor"))
    )
    (comp (ref "R26")
      (value "10 kOhms")
      (footprint "RES 0402_1005")
      (description "RES 10K OHM 1% 1/16W 0402")
      (fields
        (field (name "PART NUMBER") "RMCF0402FT10K0")
        (field (name "MANUFACTURER") "Stackpole Electronics Inc")
      )
      (libsource (lib "Celestial Altium Library - altium_library") (part "Resistor"))
    )
    (comp (ref "R27")
      (value "10 kOhms")
      (footprint "RES 0402_1005")
      (description "RES 10K OHM 1% 1/16W 0402")
      (fields
        (field (name "PART NUMBER") "RMCF0402FT10K0")
        (field (name "MANUFACTURER") "Stackpole Electronics Inc")
      )
      (libsource (lib "Celestial Altium Library - altium_library") (part "Resistor"))
    )
    (comp (ref "R28")
      (value "100 Ohms")
      (footprint "RES 0402_1005")
      (description "RES 100 OHM 1% 1/8W 0402")
      (fields
        (field (name "PART NUMBER") "CRGP0402F100R")
        (field (name "MANUFACTURER") "TE Connectivity Passive Product")
      )
      (libsource (lib "Celestial Altium Library - altium_library") (part "Resistor"))
    )
    (comp (ref "R29")
      (value "2.4 kOhms")
      (footprint "RES 0402_1005")
      (description "RES 2.4K OHM 1% 1/16W 0402")
      (fields (field (name "PART NUMBER") "RC0402FR-072K4L") (field (name "MANUFACTURER") "Yageo"))
      (libsource (lib "Celestial Altium Library - altium_library") (part "Resistor"))
    )
    (comp (ref "R30")
      (value "1 kOhms")
      (footprint "RES 0402_1005")
      (description "RES SMD 1K OHM 1% 1/16W 0402")
      (fields (field (name "PART NUMBER") "CR0402-FX-1001GLF") (field (name "MANUFACTURER") "Bourns Inc."))
      (libsource (lib "Celestial Altium Library - altium_library") (part "Resistor"))
    )
    (comp (ref "R31")
      (value "2.4 kOhms")
      (footprint "RES 0402_1005")
      (description "RES 2.4K OHM 1% 1/16W 0402")
      (fields (field (name "PART NUMBER") "RC0402FR-072K4L") (field (name "MANUFACTURER") "Yageo"))
      (libsource (lib "Celestial Altium Library - altium_library") (part "Resistor"))
    )
    (comp (ref "R32")
      (value "330 Ohms")
      (footprint "RES 0402_1005")
      (description "RES 330 OHM 1% 1/16W 0402")
      (fields
        (field (name "PART NUMBER") "RMCF0402FT330R")
        (field (name "MANUFACTURER") "Stackpole Electronics Inc")
      )
      (libsource (lib "Celestial Altium Library - altium_library") (part "Resistor"))
    )
    (comp (ref "R33")
      (value "330 Ohms")
      (footprint "RES 0402_1005")
      (description "RES 330 OHM 1% 1/16W 0402")
      (fields
        (field (name "PART NUMBER") "RMCF0402FT330R")
        (field (name "MANUFACTURER") "Stackpole Electronics Inc")
      )
      (libsource (lib "Celestial Altium Library - altium_library") (part "Resistor"))
    )
    (comp (ref "R34")
      (value "330 Ohms")
      (footprint "RES 0402_1005")
      (description "RES 330 OHM 1% 1/16W 0402")
      (fields
        (field (name "PART NUMBER") "RMCF0402FT330R")
        (field (name "MANUFACTURER") "Stackpole Electronics Inc")
      )
      (libsource (lib "Celestial Altium Library - altium_library") (part "Resistor"))
    )
    (comp (ref "R35")
      (value "10 kOhms")
      (footprint "RES 0402_1005")
      (description "RES 10K OHM 1% 1/16W 0402")
      (fields
        (field (name "PART NUMBER") "RMCF0402FT10K0")
        (field (name "MANUFACTURER") "Stackpole Electronics Inc")
      )
      (libsource (lib "Celestial Altium Library - altium_library") (part "Resistor"))
    )
    (comp (ref "R36")
      (value "10 kOhms")
      (footprint "RES 0402_1005")
      (description "RES 10K OHM 1% 1/16W 0402")
      (fields
        (field (name "PART NUMBER") "RMCF0402FT10K0")
        (field (name "MANUFACTURER") "Stackpole Electronics Inc")
      )
      (libsource (lib "Celestial Altium Library - altium_library") (part "Resistor"))
    )
    (comp (ref "R37")
      (value "10 kOhms")
      (footprint "RES 0402_1005")
      (description "RES 10K OHM 1% 1/16W 0402")
      (fields
        (field (name "PART NUMBER") "RMCF0402FT10K0")
        (field (name "MANUFACTURER") "Stackpole Electronics Inc")
      )
      (libsource (lib "Celestial Altium Library - altium_library") (part "Resistor"))
    )
    (comp (ref "R38")
      (value "10 kOhms")
      (footprint "RES 0402_1005")
      (description "RES 10K OHM 1% 1/16W 0402")
      (fields
        (field (name "PART NUMBER") "RMCF0402FT10K0")
        (field (name "MANUFACTURER") "Stackpole Electronics Inc")
      )
      (libsource (lib "Celestial Altium Library - altium_library") (part "Resistor"))
    )
    (comp (ref "R39")
      (value "10 kOhms")
      (footprint "RES 0402_1005")
      (description "RES 10K OHM 1% 1/16W 0402")
      (fields
        (field (name "PART NUMBER") "RMCF0402FT10K0")
        (field (name "MANUFACTURER") "Stackpole Electronics Inc")
      )
      (libsource (lib "Celestial Altium Library - altium_library") (part "Resistor"))
    )
    (comp (ref "R40")
      (value "10 kOhms")
      (footprint "RES 0402_1005")
      (description "RES 10K OHM 1% 1/16W 0402")
      (fields
        (field (name "PART NUMBER") "RMCF0402FT10K0")
        (field (name "MANUFACTURER") "Stackpole Electronics Inc")
      )
      (libsource (lib "Celestial Altium Library - altium_library") (part "Resistor"))
    )
    (comp (ref "R41")
      (value "10 kOhms")
      (footprint "RES 0402_1005")
      (description "RES 10K OHM 1% 1/16W 0402")
      (fields
        (field (name "PART NUMBER") "RMCF0402FT10K0")
        (field (name "MANUFACTURER") "Stackpole Electronics Inc")
      )
      (libsource (lib "Celestial Altium Library - altium_library") (part "Resistor"))
    )
    (comp (ref "R42")
      (value "10 kOhms")
      (footprint "RES 0402_1005")
      (description "RES 10K OHM 1% 1/16W 0402")
      (fields
        (field (name "PART NUMBER") "RMCF0402FT10K0")
        (field (name "MANUFACTURER") "Stackpole Electronics Inc")
      )
      (libsource (lib "Celestial Altium Library - altium_library") (part "Resistor"))
    )
    (comp (ref "R43")
      (value "10 kOhms")
      (footprint "RES 0402_1005")
      (description "RES 10K OHM 1% 1/16W 0402")
      (fields
        (field (name "PART NUMBER") "RMCF0402FT10K0")
        (field (name "MANUFACTURER") "Stackpole Electronics Inc")
      )
      (libsource (lib "Celestial Altium Library - altium_library") (part "Resistor"))
    )
    (comp (ref "R44")
      (value "5.1 kOhms")
      (footprint "RES 0402_1005")
      (description "RES 5.1K OHM 1% 1/16W 0402")
      (fields
        (field (name "PART NUMBER") "RMCF0402FT5K10")
        (field (name "MANUFACTURER") "Stackpole Electronics Inc")
      )
      (libsource (lib "Celestial Altium Library - altium_library") (part "Resistor"))
    )
    (comp (ref "R45")
      (value "10 kOhms")
      (footprint "RES 0402_1005")
      (description "RES 10K OHM 1% 1/16W 0402")
      (fields
        (field (name "PART NUMBER") "RMCF0402FT10K0")
        (field (name "MANUFACTURER") "Stackpole Electronics Inc")
      )
      (libsource (lib "Celestial Altium Library - altium_library") (part "Resistor"))
    )
    (comp (ref "R46")
      (value "5.1 kOhms")
      (footprint "RES 0402_1005")
      (description "RES 5.1K OHM 1% 1/16W 0402")
      (fields
        (field (name "PART NUMBER") "RMCF0402FT5K10")
        (field (name "MANUFACTURER") "Stackpole Electronics Inc")
      )
      (libsource (lib "Celestial Altium Library - altium_library") (part "Resistor"))
    )
    (comp (ref "R47")
      (value "330 Ohms")
      (footprint "RES 0402_1005")
      (description "RES 330 OHM 1% 1/16W 0402")
      (fields
        (field (name "PART NUMBER") "RMCF0402FT330R")
        (field (name "MANUFACTURER") "Stackpole Electronics Inc")
      )
      (libsource (lib "Celestial Altium Library - altium_library") (part "Resistor"))
    )
    (comp (ref "R48")
      (value "330 Ohms")
      (footprint "RES 0402_1005")
      (description "RES 330 OHM 1% 1/16W 0402")
      (fields
        (field (name "PART NUMBER") "RMCF0402FT330R")
        (field (name "MANUFACTURER") "Stackpole Electronics Inc")
      )
      (libsource (lib "Celestial Altium Library - altium_library") (part "Resistor"))
    )
    (comp (ref "R49")
      (value "10 Ohms")
      (footprint "RES 0402_1005")
      (description "RES 10 OHM 1% 1/8W 0402")
      (fields (field (name "PART NUMBER") "RC0402FR-7W10RL") (field (name "MANUFACTURER") "Yageo"))
      (libsource (lib "Celestial Altium Library - altium_library") (part "Resistor"))
    )
    (comp (ref "R50")
      (value "10 Ohms")
      (footprint "RES 0402_1005")
      (description "RES 10 OHM 1% 1/8W 0402")
      (fields (field (name "PART NUMBER") "RC0402FR-7W10RL") (field (name "MANUFACTURER") "Yageo"))
      (libsource (lib "Celestial Altium Library - altium_library") (part "Resistor"))
    )
    (comp (ref "R51")
      (value "10 Ohms")
      (footprint "RES 0402_1005")
      (description "RES 10 OHM 1% 1/8W 0402")
      (fields (field (name "PART NUMBER") "RC0402FR-7W10RL") (field (name "MANUFACTURER") "Yageo"))
      (libsource (lib "Celestial Altium Library - altium_library") (part "Resistor"))
    )
    (comp (ref "R52")
      (value "10 Ohms")
      (footprint "RES 0402_1005")
      (description "RES 10 OHM 1% 1/8W 0402")
      (fields (field (name "PART NUMBER") "RC0402FR-7W10RL") (field (name "MANUFACTURER") "Yageo"))
      (libsource (lib "Celestial Altium Library - altium_library") (part "Resistor"))
    )
    (comp (ref "R53")
      (value "330 Ohms")
      (footprint "RES 0402_1005")
      (description "RES 330 OHM 1% 1/16W 0402")
      (fields
        (field (name "PART NUMBER") "RMCF0402FT330R")
        (field (name "MANUFACTURER") "Stackpole Electronics Inc")
      )
      (libsource (lib "Celestial Altium Library - altium_library") (part "Resistor"))
    )
    (comp (ref "R54")
      (value "15 Ohms")
      (footprint "RES 0603_1608")
      (description "RES 15 OHM 5% 1/10W 0603")
      (fields (field (name "PART NUMBER") "RC0603JR-0715RL") (field (name "MANUFACTURER") "Yageo"))
      (libsource (lib "Celestial Altium Library - altium_library") (part "Resistor"))
    )
    (comp (ref "R55")
      (value "330 Ohms")
      (footprint "RES 0402_1005")
      (description "RES 330 OHM 1% 1/16W 0402")
      (fields
        (field (name "PART NUMBER") "RMCF0402FT330R")
        (field (name "MANUFACTURER") "Stackpole Electronics Inc")
      )
      (libsource (lib "Celestial Altium Library - altium_library") (part "Resistor"))
    )
    (comp (ref "R56")
      (value "10 kOhms")
      (footprint "RES 0402_1005")
      (description "RES 10K OHM 1% 1/16W 0402")
      (fields
        (field (name "PART NUMBER") "RMCF0402FT10K0")
        (field (name "MANUFACTURER") "Stackpole Electronics Inc")
      )
      (libsource (lib "Celestial Altium Library - altium_library") (part "Resistor"))
    )
    (comp (ref "R57")
      (value "1 kOhms")
      (footprint "RES 0402_1005")
      (description "RES SMD 1K OHM 1% 1/16W 0402")
      (fields (field (name "PART NUMBER") "CR0402-FX-1001GLF") (field (name "MANUFACTURER") "Bourns Inc."))
      (libsource (lib "Celestial Altium Library - altium_library") (part "Resistor"))
    )
    (comp (ref "R58")
      (value "1 kOhms")
      (footprint "RES 0402_1005")
      (description "RES SMD 1K OHM 1% 1/16W 0402")
      (fields (field (name "PART NUMBER") "CR0402-FX-1001GLF") (field (name "MANUFACTURER") "Bourns Inc."))
      (libsource (lib "Celestial Altium Library - altium_library") (part "Resistor"))
    )
    (comp (ref "R59")
      (value "1 kOhms")
      (footprint "RES 0402_1005")
      (description "RES SMD 1K OHM 1% 1/16W 0402")
      (fields (field (name "PART NUMBER") "CR0402-FX-1001GLF") (field (name "MANUFACTURER") "Bourns Inc."))
      (libsource (lib "Celestial Altium Library - altium_library") (part "Resistor"))
    )
    (comp (ref "R60")
      (value "10 kOhms")
      (footprint "RES 0402_1005")
      (description "RES 10K OHM 1% 1/16W 0402")
      (fields
        (field (name "PART NUMBER") "RMCF0402FT10K0")
        (field (name "MANUFACTURER") "Stackpole Electronics Inc")
      )
      (libsource (lib "Celestial Altium Library - altium_library") (part "Resistor"))
    )
    (comp (ref "R61")
      (value "30 kOhms")
      (footprint "RES 0402_1005")
      (description "RES 30K OHM 1% 1/16W 0402")
      (fields (field (name "PART NUMBER") "RC0402FR-0730KL") (field (name "MANUFACTURER") "Yageo"))
      (libsource (lib "Celestial Altium Library - altium_library") (part "Resistor"))
    )
    (comp (ref "R62")
      (value "30 kOhms")
      (footprint "RES 0402_1005")
      (description "RES 30K OHM 1% 1/16W 0402")
      (fields (field (name "PART NUMBER") "RC0402FR-0730KL") (field (name "MANUFACTURER") "Yageo"))
      (libsource (lib "Celestial Altium Library - altium_library") (part "Resistor"))
    )
    (comp (ref "R63")
      (value "30 kOhms")
      (footprint "RES 0402_1005")
      (description "RES 30K OHM 1% 1/16W 0402")
      (fields (field (name "PART NUMBER") "RC0402FR-0730KL") (field (name "MANUFACTURER") "Yageo"))
      (libsource (lib "Celestial Altium Library - altium_library") (part "Resistor"))
    )
    (comp (ref "R64")
      (value "30 kOhms")
      (footprint "RES 0402_1005")
      (description "RES 30K OHM 1% 1/16W 0402")
      (fields (field (name "PART NUMBER") "RC0402FR-0730KL") (field (name "MANUFACTURER") "Yageo"))
      (libsource (lib "Celestial Altium Library - altium_library") (part "Resistor"))
    )
    (comp (ref "R65")
      (value "30 kOhms")
      (footprint "RES 0402_1005")
      (description "RES 30K OHM 1% 1/16W 0402")
      (fields (field (name "PART NUMBER") "RC0402FR-0730KL") (field (name "MANUFACTURER") "Yageo"))
      (libsource (lib "Celestial Altium Library - altium_library") (part "Resistor"))
    )
    (comp (ref "R66")
      (value "30 kOhms")
      (footprint "RES 0402_1005")
      (description "RES 30K OHM 1% 1/16W 0402")
      (fields (field (name "PART NUMBER") "RC0402FR-0730KL") (field (name "MANUFACTURER") "Yageo"))
      (libsource (lib "Celestial Altium Library - altium_library") (part "Resistor"))
    )
    (comp (ref "R67")
      (value "30 kOhms")
      (footprint "RES 0402_1005")
      (description "RES 30K OHM 1% 1/16W 0402")
      (fields (field (name "PART NUMBER") "RC0402FR-0730KL") (field (name "MANUFACTURER") "Yageo"))
      (libsource (lib "Celestial Altium Library - altium_library") (part "Resistor"))
    )
    (comp (ref "R68")
      (value "30 kOhms")
      (footprint "RES 0402_1005")
      (description "RES 30K OHM 1% 1/16W 0402")
      (fields (field (name "PART NUMBER") "RC0402FR-0730KL") (field (name "MANUFACTURER") "Yageo"))
      (libsource (lib "Celestial Altium Library - altium_library") (part "Resistor"))
    )
    (comp (ref "TP1")
      (value "TestPoint")
      (footprint "TestPoint1")
      (libsource (lib "SamacSys") (part "TestPoint"))
    )
    (comp (ref "TP2")
      (value "TestPoint")
      (footprint "TestPoint1")
      (libsource (lib "SamacSys") (part "TestPoint"))
    )
    (comp (ref "U1")
      (value "LM27313XMF")
      (footprint "SamacSys:SOT95P280X145-5N")
      (description "Integrated Circuit")
      (fields (field (name "MOUSER PART NUMBER") "926-LM27313XMF"))
      (libsource (lib "*") (part "LM27313XMF"))
    )
    (comp (ref "U2")
      (value "LM27313XMF")
      (footprint "SamacSys:SOT95P280X145-5N")
      (description "Integrated Circuit")
      (fields (field (name "MOUSER PART NUMBER") "926-LM27313XMF"))
      (libsource (lib "*") (part "LM27313XMF"))
    )
    (comp (ref "Y1")
      (value "8MHZ")
      (footprint "SamacSys:NX3225GD8MHZSTDCRA3")
      (description "Crystal or Oscillator")
      (fields
        (field (name "MANUFACTURER_PART_NUMBER") "NX3225GD-8MHZ-STD-CRA-3")
        (field (name "MOUSER PART NUMBER") "344-NX3225GD8MCRA3")
      )
      (libsource (lib "SamacSys") (part "NX3225GD-8MHZ-STD-CRA-3"))
    )
  )
  (nets
    (net (code "1") (name "+3.3V_A") (class "Default")
      (node (ref "B1") (pin "13") (pinfunction "VDDA/VREF+_13") (pintype "passive"))
      (node (ref "C17") (pin "1") (pinfunction "1_1") (pintype "passive"))
      (node (ref "C19") (pin "2") (pinfunction "2_2") (pintype "passive"))
      (node (ref "L4") (pin "2") (pinfunction "2_2") (pintype "passive"))
    )
    (net (code "2") (name "+3.3V_D") (class "Default")
      (node (ref "B1") (pin "19") (pinfunction "VDD_1_19") (pintype "passive"))
      (node (ref "B1") (pin "32") (pinfunction "VDD_2_32") (pintype "passive"))
      (node (ref "B1") (pin "48") (pinfunction "VDD_3_48") (pintype "passive"))
      (node (ref "B1") (pin "64") (pinfunction "VDD_4_64") (pintype "passive"))
      (node (ref "B2") (pin "11") (pinfunction "VDDP_11") (pintype "passive"))
      (node (ref "B2") (pin "14") (pinfunction "WM_14") (pintype "passive"))
      (node (ref "C11") (pin "2") (pinfunction "2_2") (pintype "passive"))
      (node (ref "C21") (pin "2") (pinfunction "2_2") (pintype "passive"))
      (node (ref "C22") (pin "2") (pinfunction "2_2") (pintype "passive"))
      (node (ref "C23") (pin "2") (pinfunction "2_2") (pintype "passive"))
      (node (ref "C24") (pin "2") (pinfunction "2_2") (pintype "passive"))
      (node (ref "C25") (pin "2") (pinfunction "2_2") (pintype "passive"))
      (node (ref "C29") (pin "2") (pinfunction "2_2") (pintype "passive"))
      (node (ref "C30") (pin "2") (pinfunction "2_2") (pintype "passive"))
      (node (ref "C31") (pin "2") (pinfunction "2_2") (pintype "passive"))
      (node (ref "C32") (pin "2") (pinfunction "2_2") (pintype "passive"))
      (node (ref "C33") (pin "2") (pinfunction "2_2") (pintype "passive"))
      (node (ref "C34") (pin "2") (pinfunction "2_2") (pintype "passive"))
      (node (ref "C35") (pin "2") (pinfunction "2_2") (pintype "passive"))
      (node (ref "C36") (pin "1") (pinfunction "1_1") (pintype "passive"))
      (node (ref "C40") (pin "1") (pinfunction "1_1") (pintype "passive"))
      (node (ref "C41") (pin "1") (pinfunction "1_1") (pintype "passive"))
      (node (ref "C42") (pin "2") (pinfunction "2_2") (pintype "passive"))
      (node (ref "C8") (pin "1") (pinfunction "1_1") (pintype "passive"))
      (node (ref "D8") (pin "2") (pinfunction "2_2") (pintype "passive"))
      (node (ref "IC2") (pin "3") (pinfunction "FEEDBACK_3") (pintype "passive"))
      (node (ref "IC4") (pin "9") (pinfunction "VBAT_9") (pintype "passive"))
      (node (ref "IC5") (pin "5") (pinfunction "V+_5") (pintype "passive"))
      (node (ref "IC6") (pin "1") (pinfunction "RESV_1_1") (pintype "passive"))
      (node (ref "IC6") (pin "13") (pinfunction "VDD_13") (pintype "passive"))
      (node (ref "IC6") (pin "8") (pinfunction "VDDIO_8") (pintype "passive"))
      (node (ref "J3") (pin "7") (pinfunction "7_7") (pintype "passive"))
      (node (ref "J5") (pin "7") (pinfunction "7_7") (pintype "passive"))
      (node (ref "J5") (pin "8") (pinfunction "8_8") (pintype "passive"))
      (node (ref "L3") (pin "2") (pinfunction "2_2") (pintype "passive"))
      (node (ref "L4") (pin "1") (pinfunction "1_1") (pintype "passive"))
      (node (ref "R16") (pin "2") (pinfunction "2_2") (pintype "passive"))
      (node (ref "R30") (pin "1") (pinfunction "1_1") (pintype "passive"))
      (node (ref "R4") (pin "2") (pinfunction "2_2") (pintype "passive"))
      (node (ref "R44") (pin "2") (pinfunction "2_2") (pintype "passive"))
      (node (ref "R46") (pin "1") (pinfunction "1_1") (pintype "passive"))
      (node (ref "R54") (pin "2") (pinfunction "2_2") (pintype "passive"))
      (node (ref "R63") (pin "1") (pinfunction "1_1") (pintype "passive"))
      (node (ref "R67") (pin "1") (pinfunction "1_1") (pintype "passive"))
    )
    (net (code "3") (name "+5V") (class "Default")
      (node (ref "C1") (pin "2") (pinfunction "2_2") (pintype "passive"))
      (node (ref "C10") (pin "2") (pinfunction "2_2") (pintype "passive"))
      (node (ref "C39") (pin "2") (pinfunction "2_2") (pintype "passive"))
      (node (ref "C5") (pin "2") (pinfunction "2_2") (pintype "passive"))
      (node (ref "C7") (pin "1") (pinfunction "1_1") (pintype "passive"))
      (node (ref "D3") (pin "2") (pinfunction "2_2") (pintype "passive"))
      (node (ref "IC2") (pin "1") (pinfunction "VIN_1") (pintype "passive"))
      (node (ref "LED1") (pin "1") (pinfunction "VDD_1") (pintype "passive"))
      (node (ref "R10") (pin "2") (pinfunction "2_2") (pintype "passive"))
    )
    (net (code "4") (name "ADC_IN10") (class "Default")
      (node (ref "B1") (pin "8") (pinfunction "PC0_8") (pintype "passive"))
      (node (ref "C26") (pin "1") (pinfunction "1_1") (pintype "passive"))
      (node (ref "R38") (pin "1") (pinfunction "1_1") (pintype "passive"))
    )
    (net (code "5") (name "ADC_IN11") (class "Default")
      (node (ref "B1") (pin "9") (pinfunction "PC1_9") (pintype "passive"))
      (node (ref "C27") (pin "1") (pinfunction "1_1") (pintype "passive"))
      (node (ref "R39") (pin "1") (pinfunction "1_1") (pintype "passive"))
      (node (ref "TP2") (pin "1") (pinfunction "1_1") (pintype "passive"))
    )
    (net (code "6") (name "ADC_IN12") (class "Default")
      (node (ref "B1") (pin "10") (pinfunction "PC2_10") (pintype "passive"))
      (node (ref "C28") (pin "1") (pinfunction "1_1") (pintype "passive"))
      (node (ref "R40") (pin "1") (pinfunction "1_1") (pintype "passive"))
    )
    (net (code "7") (name "BLE_F") (class "Default")
      (node (ref "B1") (pin "26") (pinfunction "PB0_26") (pintype "passive"))
      (node (ref "R34") (pin "1") (pinfunction "1_1") (pintype "passive"))
    )
    (net (code "8") (name "BLE_HYB") (class "Default")
      (node (ref "B1") (pin "24") (pinfunction "PC4_24") (pintype "passive"))
      (node (ref "R33") (pin "1") (pinfunction "1_1") (pintype "passive"))
    )
    (net (code "9") (name "BLE_RESET") (class "Default")
      (node (ref "B1") (pin "11") (pinfunction "PC3_11") (pintype "passive"))
      (node (ref "R25") (pin "2") (pinfunction "2_2") (pintype "passive"))
    )
    (net (code "10") (name "BLE_RXD") (class "Default")
      (node (ref "B1") (pin "38") (pinfunction "PC7_38") (pintype "passive"))
      (node (ref "IC4") (pin "23") (pinfunction "UART0_TXD_23") (pintype "passive"))
    )
    (net (code "11") (name "BLE_SLC") (class "Default")
      (node (ref "B1") (pin "25") (pinfunction "PC5_25") (pintype "passive"))
      (node (ref "R32") (pin "1") (pinfunction "1_1") (pintype "passive"))
    )
    (net (code "12") (name "BLE_TXD") (class "Default")
      (node (ref "B1") (pin "37") (pinfunction "PC6_37") (pintype "passive"))
      (node (ref "IC4") (pin "24") (pinfunction "UART0_RXD_24") (pintype "passive"))
    )
    (net (code "13") (name "BOOT0") (class "Default")
      (node (ref "B1") (pin "60") (pinfunction "BOOT0_60") (pintype "passive"))
      (node (ref "R17") (pin "1") (pinfunction "1_1") (pintype "passive"))
    )
    (net (code "14") (name "BUZZER") (class "Default")
      (node (ref "B1") (pin "14") (pinfunction "PA0_14") (pintype "passive"))
      (node (ref "R48") (pin "1") (pinfunction "1_1") (pintype "passive"))
    )
    (net (code "15") (name "CON_DEBUG_TX") (class "Default")
      (node (ref "J3") (pin "4") (pinfunction "4_4") (pintype "passive"))
      (node (ref "R22") (pin "1") (pinfunction "1_1") (pintype "passive"))
    )
    (net (code "16") (name "CON_GYDRO_RX") (class "Default")
      (node (ref "J4") (pin "7") (pinfunction "7_7") (pintype "passive"))
      (node (ref "R52") (pin "1") (pinfunction "1_1") (pintype "passive"))
    )
    (net (code "17") (name "CON_GYDRO_TX") (class "Default")
      (node (ref "J4") (pin "8") (pinfunction "8_8") (pintype "passive"))
      (node (ref "R51") (pin "1") (pinfunction "1_1") (pintype "passive"))
    )
    (net (code "18") (name "CON_SWCLK") (class "Default")
      (node (ref "J3") (pin "5") (pinfunction "5_5") (pintype "passive"))
      (node (ref "R20") (pin "1") (pinfunction "1_1") (pintype "passive"))
    )
    (net (code "19") (name "CON_SWDIO") (class "Default")
      (node (ref "J3") (pin "6") (pinfunction "6_6") (pintype "passive"))
      (node (ref "R21") (pin "1") (pinfunction "1_1") (pintype "passive"))
    )
    (net (code "20") (name "CON_TENZO_RX") (class "Default")
      (node (ref "J5") (pin "2") (pinfunction "2_2") (pintype "passive"))
      (node (ref "R50") (pin "1") (pinfunction "1_1") (pintype "passive"))
    )
    (net (code "21") (name "CON_TENZO_TX") (class "Default")
      (node (ref "J5") (pin "1") (pinfunction "1_1") (pintype "passive"))
      (node (ref "R49") (pin "1") (pinfunction "1_1") (pintype "passive"))
    )
    (net (code "22") (name "DCharge") (class "Default")
      (node (ref "B1") (pin "4") (pinfunction "PC15-OSC32_OUT_4") (pintype "passive"))
      (node (ref "R24") (pin "2") (pinfunction "2_2") (pintype "passive"))
    )
    (net (code "23") (name "DEBUG_LED1") (class "Default")
      (node (ref "B1") (pin "36") (pinfunction "PB15_36") (pintype "passive"))
      (node (ref "D5") (pin "1") (pinfunction "1_1") (pintype "passive"))
    )
    (net (code "24") (name "DEBUG_LED2") (class "Default")
      (node (ref "B1") (pin "35") (pinfunction "PB14_35") (pintype "passive"))
      (node (ref "D6") (pin "1") (pinfunction "1_1") (pintype "passive"))
    )
    (net (code "25") (name "DEBUG_LED3") (class "Default")
      (node (ref "B1") (pin "34") (pinfunction "PB13_34") (pintype "passive"))
      (node (ref "D7") (pin "1") (pinfunction "1_1") (pintype "passive"))
    )
    (net (code "26") (name "DEBUG_TX") (class "Default")
      (node (ref "B1") (pin "42") (pinfunction "PA9_42") (pintype "passive"))
      (node (ref "R22") (pin "2") (pinfunction "2_2") (pintype "passive"))
    )
    (net (code "27") (name "DVibro") (class "Default")
      (node (ref "B1") (pin "62") (pinfunction "PB9_62") (pintype "passive"))
      (node (ref "R55") (pin "2") (pinfunction "2_2") (pintype "passive"))
    )
    (net (code "28") (name "GND") (class "Default")
      (node (ref "B1") (pin "18") (pinfunction "VSS_1_18") (pintype "passive"))
      (node (ref "B1") (pin "31") (pinfunction "VSS_2_31") (pintype "passive"))
      (node (ref "B1") (pin "47") (pinfunction "VSS_3_47") (pintype "passive"))
      (node (ref "B1") (pin "63") (pinfunction "VSS_4_63") (pintype "passive"))
      (node (ref "B2") (pin "10") (pinfunction "~{EN_INT}_10") (pintype "passive"))
      (node (ref "B2") (pin "13") (pinfunction "VSS_13") (pintype "passive"))
      (node (ref "B2") (pin "9") (pinfunction "TEST_9") (pintype "passive"))
      (node (ref "C1") (pin "1") (pinfunction "1_1") (pintype "passive"))
      (node (ref "C10") (pin "1") (pinfunction "1_1") (pintype "passive"))
      (node (ref "C11") (pin "1") (pinfunction "1_1") (pintype "passive"))
      (node (ref "C12") (pin "1") (pinfunction "1_1") (pintype "passive"))
      (node (ref "C13") (pin "1") (pinfunction "1_1") (pintype "passive"))
      (node (ref "C14") (pin "2") (pinfunction "2_2") (pintype "passive"))
      (node (ref "C15") (pin "2") (pinfunction "2_2") (pintype "passive"))
      (node (ref "C16") (pin "1") (pinfunction "1_1") (pintype "passive"))
      (node (ref "C2") (pin "1") (pinfunction "1_1") (pintype "passive"))
      (node (ref "C20") (pin "1") (pinfunction "1_1") (pintype "passive"))
      (node (ref "C21") (pin "1") (pinfunction "1_1") (pintype "passive"))
      (node (ref "C22") (pin "1") (pinfunction "1_1") (pintype "passive"))
      (node (ref "C23") (pin "1") (pinfunction "1_1") (pintype "passive"))
      (node (ref "C24") (pin "1") (pinfunction "1_1") (pintype "passive"))
      (node (ref "C25") (pin "1") (pinfunction "1_1") (pintype "passive"))
      (node (ref "C26") (pin "2") (pinfunction "2_2") (pintype "passive"))
      (node (ref "C27") (pin "2") (pinfunction "2_2") (pintype "passive"))
      (node (ref "C28") (pin "2") (pinfunction "2_2") (pintype "passive"))
      (node (ref "C29") (pin "1") (pinfunction "1_1") (pintype "passive"))
      (node (ref "C3") (pin "1") (pinfunction "1_1") (pintype "passive"))
      (node (ref "C30") (pin "1") (pinfunction "1_1") (pintype "passive"))
      (node (ref "C31") (pin "1") (pinfunction "1_1") (pintype "passive"))
      (node (ref "C32") (pin "1") (pinfunction "1_1") (pintype "passive"))
      (node (ref "C34") (pin "1") (pinfunction "1_1") (pintype "passive"))
      (node (ref "C35") (pin "1") (pinfunction "1_1") (pintype "passive"))
      (node (ref "C36") (pin "2") (pinfunction "2_2") (pintype "passive"))
      (node (ref "C37") (pin "1") (pinfunction "1_1") (pintype "passive"))
      (node (ref "C38") (pin "2") (pinfunction "2_2") (pintype "passive"))
      (node (ref "C39") (pin "1") (pinfunction "1_1") (pintype "passive"))
      (node (ref "C40") (pin "2") (pinfunction "2_2") (pintype "passive"))
      (node (ref "C41") (pin "2") (pinfunction "2_2") (pintype "passive"))
      (node (ref "C6") (pin "2") (pinfunction "2_2") (pintype "passive"))
      (node (ref "C7") (pin "2") (pinfunction "2_2") (pintype "passive"))
      (node (ref "C8") (pin "2") (pinfunction "2_2") (pintype "passive"))
      (node (ref "C9") (pin "1") (pinfunction "1_1") (pintype "passive"))
      (node (ref "D1") (pin "1") (pinfunction "1_1") (pintype "passive"))
      (node (ref "IC1") (pin "2") (pinfunction "GND_2") (pintype "passive"))
      (node (ref "IC2") (pin "4") (pinfunction "ON/OFF_4") (pintype "passive"))
      (node (ref "IC2") (pin "5") (pinfunction "GND_1_5") (pintype "passive"))
      (node (ref "IC2") (pin "6") (pinfunction "GND_2_6") (pintype "passive"))
      (node (ref "IC2") (pin "7") (pinfunction "GND_3_7") (pintype "passive"))
      (node (ref "IC2") (pin "8") (pinfunction "GND_4_8") (pintype "passive"))
      (node (ref "IC2") (pin "9") (pinfunction "BPAD_9") (pintype "passive"))
      (node (ref "IC4") (pin "1") (pinfunction "GND_1") (pintype "passive"))
      (node (ref "IC4") (pin "10") (pinfunction "GND_10") (pintype "passive"))
      (node (ref "IC4") (pin "28") (pinfunction "GND_28") (pintype "passive"))
      (node (ref "IC6") (pin "18") (pinfunction "GND_18") (pintype "passive"))
      (node (ref "IC6") (pin "20") (pinfunction "RESV_3_20") (pintype "passive"))
      (node (ref "J1") (pin "A1_B12") (pinfunction "GND_A1_B12") (pintype "power_in"))
      (node (ref "J1") (pin "B1_A12") (pinfunction "GND_B1_A12") (pintype "power_in"))
      (node (ref "J1") (pin "SH1") (pinfunction "SHELL_GND_SH1") (pintype "power_in"))
      (node (ref "J1") (pin "SH2") (pinfunction "SHELL_GND_SH2") (pintype "power_in"))
      (node (ref "J1") (pin "SH3") (pinfunction "SHELL_GND_SH3") (pintype "power_in"))
      (node (ref "J1") (pin "SH4") (pinfunction "SHELL_GND_SH4") (pintype "power_in"))
      (node (ref "J2") (pin "1") (pinfunction "TEMP1_1") (pintype "passive"))
      (node (ref "J2") (pin "3") (pinfunction "GND_3_3") (pintype "passive"))
      (node (ref "J2") (pin "9") (pinfunction "EP_9") (pintype "passive"))
      (node (ref "J3") (pin "9") (pinfunction "9_9") (pintype "passive"))
      (node (ref "J3") (pin "MP1") (pinfunction "MP1_MP1") (pintype "passive"))
      (node (ref "J3") (pin "MP2") (pinfunction "MP2_MP2") (pintype "passive"))
      (node (ref "J4") (pin "3") (pinfunction "3_3") (pintype "passive"))
      (node (ref "J4") (pin "4") (pinfunction "4_4") (pintype "passive"))
      (node (ref "J4") (pin "5") (pinfunction "5_5") (pintype "passive"))
      (node (ref "J4") (pin "MP1") (pinfunction "MP1_MP1") (pintype "passive"))
      (node (ref "J4") (pin "MP2") (pinfunction "MP2_MP2") (pintype "passive"))
      (node (ref "J5") (pin "4") (pinfunction "4_4") (pintype "passive"))
      (node (ref "J5") (pin "5") (pinfunction "5_5") (pintype "passive"))
      (node (ref "J5") (pin "6") (pinfunction "6_6") (pintype "passive"))
      (node (ref "J5") (pin "MP1") (pinfunction "MP1_MP1") (pintype "passive"))
      (node (ref "J5") (pin "MP2") (pinfunction "MP2_MP2") (pintype "passive"))
      (node (ref "LED1") (pin "3") (pinfunction "VSS_3") (pintype "passive"))
      (node (ref "Q1") (pin "3") (pinfunction "S2_3") (pintype "passive"))
      (node (ref "Q2") (pin "2") (pinfunction "S_2") (pintype "passive"))
      (node (ref "Q3") (pin "2") (pinfunction "S_2") (pintype "passive"))
      (node (ref "Q4") (pin "2") (pinfunction "S_2") (pintype "passive"))
      (node (ref "R1") (pin "2") (pinfunction "2_2") (pintype "passive"))
      (node (ref "R11") (pin "2") (pinfunction "2_2") (pintype "passive"))
      (node (ref "R17") (pin "2") (pinfunction "2_2") (pintype "passive"))
      (node (ref "R19") (pin "1") (pinfunction "1_1") (pintype "passive"))
      (node (ref "R23") (pin "1") (pinfunction "1_1") (pintype "passive"))
      (node (ref "R26") (pin "2") (pinfunction "2_2") (pintype "passive"))
      (node (ref "R27") (pin "2") (pinfunction "2_2") (pintype "passive"))
      (node (ref "R31") (pin "1") (pinfunction "1_1") (pintype "passive"))
      (node (ref "R35") (pin "1") (pinfunction "1_1") (pintype "passive"))
      (node (ref "R36") (pin "1") (pinfunction "1_1") (pintype "passive"))
      (node (ref "R37") (pin "1") (pinfunction "1_1") (pintype "passive"))
      (node (ref "R45") (pin "1") (pinfunction "1_1") (pintype "passive"))
      (node (ref "R5") (pin "2") (pinfunction "2_2") (pintype "passive"))
      (node (ref "R56") (pin "2") (pinfunction "2_2") (pintype "passive"))
      (node (ref "R57") (pin "2") (pinfunction "2_2") (pintype "passive"))
      (node (ref "R58") (pin "2") (pinfunction "2_2") (pintype "passive"))
      (node (ref "R59") (pin "2") (pinfunction "2_2") (pintype "passive"))
      (node (ref "R60") (pin "2") (pinfunction "2_2") (pintype "passive"))
      (node (ref "R61") (pin "1") (pinfunction "1_1") (pintype "passive"))
      (node (ref "R62") (pin "1") (pinfunction "1_1") (pintype "passive"))
      (node (ref "R64") (pin "1") (pinfunction "1_1") (pintype "passive"))
      (node (ref "R65") (pin "1") (pinfunction "1_1") (pintype "passive"))
      (node (ref "R66") (pin "1") (pinfunction "1_1") (pintype "passive"))
      (node (ref "R68") (pin "1") (pinfunction "1_1") (pintype "passive"))
      (node (ref "R9") (pin "2") (pinfunction "2_2") (pintype "passive"))
      (node (ref "U1") (pin "2") (pinfunction "GND_2") (pintype "passive"))
      (node (ref "U2") (pin "2") (pinfunction "GND_2") (pintype "passive"))
    )
    (net (code "29") (name "GNDA") (class "Default")
      (node (ref "B1") (pin "12") (pinfunction "VSSA/VREF-_12") (pintype "passive"))
      (node (ref "C17") (pin "2") (pinfunction "2_2") (pintype "passive"))
      (node (ref "C19") (pin "1") (pinfunction "1_1") (pintype "passive"))
      (node (ref "R23") (pin "2") (pinfunction "2_2") (pintype "passive"))
    )
    (net (code "30") (name "GND_TRM") (class "Default")
      (node (ref "C33") (pin "1") (pinfunction "1_1") (pintype "passive"))
      (node (ref "IC5") (pin "2") (pinfunction "GND_2") (pintype "passive"))
      (node (ref "IC5") (pin "4") (pinfunction "ADD0_4") (pintype "passive"))
      (node (ref "Q3") (pin "3") (pinfunction "D_3") (pintype "passive"))
    )
    (net (code "31") (name "GYDRO_RX") (class "Default")
      (node (ref "B1") (pin "52") (pinfunction "PC11_52") (pintype "passive"))
      (node (ref "R51") (pin "2") (pinfunction "2_2") (pintype "passive"))
    )
    (net (code "32") (name "GYDRO_TX") (class "Default")
      (node (ref "B1") (pin "51") (pinfunction "PC10_51") (pintype "passive"))
      (node (ref "R52") (pin "2") (pinfunction "2_2") (pintype "passive"))
    )
    (net (code "33") (name "GYRO_CLK") (class "Default")
      (node (ref "B1") (pin "21") (pinfunction "PA5_21") (pintype "passive"))
      (node (ref "IC6") (pin "23") (pinfunction "SCL_/_SCLK_23") (pintype "passive"))
      (node (ref "R61") (pin "2") (pinfunction "2_2") (pintype "passive"))
    )
    (net (code "34") (name "GYRO_MISO") (class "Default")
      (node (ref "B1") (pin "22") (pinfunction "PA6_22") (pintype "passive"))
      (node (ref "IC6") (pin "9") (pinfunction "AD0/SDO_9") (pintype "passive"))
      (node (ref "R64") (pin "2") (pinfunction "2_2") (pintype "passive"))
    )
    (net (code "35") (name "GYRO_MOSI") (class "Default")
      (node (ref "B1") (pin "23") (pinfunction "PA7_23") (pintype "passive"))
      (node (ref "IC6") (pin "24") (pinfunction "SDA_/_SDI_24") (pintype "passive"))
      (node (ref "R62") (pin "2") (pinfunction "2_2") (pintype "passive"))
    )
    (net (code "36") (name "GYRO_SS") (class "Default")
      (node (ref "B1") (pin "20") (pinfunction "PA4_20") (pintype "passive"))
      (node (ref "IC6") (pin "22") (pinfunction "NCS_22") (pintype "passive"))
      (node (ref "R63") (pin "2") (pinfunction "2_2") (pintype "passive"))
    )
    (net (code "37") (name "HALL_CLK") (class "Default")
      (node (ref "B1") (pin "55") (pinfunction "PB3_55") (pintype "passive"))
      (node (ref "B2") (pin "3") (pinfunction "SCK_3") (pintype "passive"))
      (node (ref "R65") (pin "2") (pinfunction "2_2") (pintype "passive"))
    )
    (net (code "38") (name "HALL_MISO") (class "Default")
      (node (ref "B1") (pin "56") (pinfunction "PB4_56") (pintype "passive"))
      (node (ref "B2") (pin "2") (pinfunction "MISO_2") (pintype "passive"))
      (node (ref "R68") (pin "2") (pinfunction "2_2") (pintype "passive"))
    )
    (net (code "39") (name "HALL_MOSI") (class "Default")
      (node (ref "B1") (pin "57") (pinfunction "PB5_57") (pintype "passive"))
      (node (ref "B2") (pin "1") (pinfunction "MOSI_1") (pintype "passive"))
      (node (ref "R66") (pin "2") (pinfunction "2_2") (pintype "passive"))
    )
    (net (code "40") (name "HALL_SS") (class "Default")
      (node (ref "B1") (pin "50") (pinfunction "PA15_50") (pintype "passive"))
      (node (ref "B2") (pin "4") (pinfunction "~{SS}_4") (pintype "passive"))
      (node (ref "R67") (pin "2") (pinfunction "2_2") (pintype "passive"))
    )
    (net (code "41") (name "I_CHARGE") (class "Default")
      (node (ref "C20") (pin "2") (pinfunction "2_2") (pintype "passive"))
      (node (ref "J2") (pin "2") (pinfunction "PROG2_2") (pintype "passive"))
      (node (ref "R29") (pin "2") (pinfunction "2_2") (pintype "passive"))
      (node (ref "R31") (pin "2") (pinfunction "2_2") (pintype "passive"))
      (node (ref "R42") (pin "2") (pinfunction "2_2") (pintype "passive"))
    )
    (net (code "42") (name "LED_SYS") (class "Default")
      (node (ref "B1") (pin "39") (pinfunction "PC8_39") (pintype "passive"))
      (node (ref "R53") (pin "1") (pinfunction "1_1") (pintype "passive"))
    )
    (net (code "43") (name "NRST") (class "Default")
      (node (ref "B1") (pin "7") (pinfunction "NRST_7") (pintype "passive"))
      (node (ref "J3") (pin "3") (pinfunction "3_3") (pintype "passive"))
      (node (ref "R16") (pin "1") (pinfunction "1_1") (pintype "passive"))
    )
    (net (code "44") (name "Net-(B2-VDD)") (class "Default")
      (node (ref "B2") (pin "12") (pinfunction "VDD_12") (pintype "passive"))
      (node (ref "C38") (pin "1") (pinfunction "1_1") (pintype "passive"))
      (node (ref "R54") (pin "1") (pinfunction "1_1") (pintype "passive"))
    )
    (net (code "45") (name "Net-(D4-Pad1)") (class "Default")
      (node (ref "D4") (pin "1") (pinfunction "1_1") (pintype "passive"))
      (node (ref "R30") (pin "2") (pinfunction "2_2") (pintype "passive"))
    )
    (net (code "46") (name "Net-(D5-Pad2)") (class "Default")
      (node (ref "D5") (pin "2") (pinfunction "2_2") (pintype "passive"))
      (node (ref "R57") (pin "1") (pinfunction "1_1") (pintype "passive"))
    )
    (net (code "47") (name "Net-(D6-Pad2)") (class "Default")
      (node (ref "D6") (pin "2") (pinfunction "2_2") (pintype "passive"))
      (node (ref "R58") (pin "1") (pinfunction "1_1") (pintype "passive"))
    )
    (net (code "48") (name "Net-(D7-Pad2)") (class "Default")
      (node (ref "D7") (pin "2") (pinfunction "2_2") (pintype "passive"))
      (node (ref "R59") (pin "1") (pinfunction "1_1") (pintype "passive"))
    )
    (net (code "49") (name "Net-(IC2-OUTPUT)") (class "Default")
      (node (ref "D1") (pin "2") (pinfunction "2_2") (pintype "passive"))
      (node (ref "IC2") (pin "2") (pinfunction "OUTPUT_2") (pintype "passive"))
      (node (ref "L3") (pin "1") (pinfunction "1_1") (pintype "passive"))
    )
    (net (code "50") (name "Net-(IC3-CS)") (class "Default")
      (node (ref "IC3") (pin "2") (pinfunction "CS_2") (pintype "passive"))
      (node (ref "R19") (pin "2") (pinfunction "2_2") (pintype "passive"))
    )
    (net (code "51") (name "Net-(IC3-OC)") (class "Default")
      (node (ref "IC3") (pin "3") (pinfunction "OC_3") (pintype "passive"))
      (node (ref "Q1") (pin "4") (pinfunction "G2_4") (pintype "passive"))
    )
    (net (code "52") (name "Net-(IC3-OD)") (class "Default")
      (node (ref "IC3") (pin "1") (pinfunction "OD_1") (pintype "passive"))
      (node (ref "Q1") (pin "6") (pinfunction "G1_6") (pintype "passive"))
    )
    (net (code "53") (name "Net-(IC3-VCC)") (class "Default")
      (node (ref "C18") (pin "1") (pinfunction "1_1") (pintype "passive"))
      (node (ref "IC3") (pin "5") (pinfunction "VCC_5") (pintype "passive"))
      (node (ref "R28") (pin "1") (pinfunction "1_1") (pintype "passive"))
    )
    (net (code "54") (name "Net-(IC4-PA4)") (class "Default")
      (node (ref "D4") (pin "2") (pinfunction "2_2") (pintype "passive"))
      (node (ref "IC4") (pin "25") (pinfunction "PA4_25") (pintype "passive"))
    )
    (net (code "55") (name "Net-(IC4-PC5)") (class "Default")
      (node (ref "IC4") (pin "18") (pinfunction "PC5_18") (pintype "passive"))
      (node (ref "R34") (pin "2") (pinfunction "2_2") (pintype "passive"))
    )
    (net (code "56") (name "Net-(IC4-PC6)") (class "Default")
      (node (ref "IC4") (pin "17") (pinfunction "PC6_17") (pintype "passive"))
      (node (ref "R33") (pin "2") (pinfunction "2_2") (pintype "passive"))
    )
    (net (code "57") (name "Net-(IC4-PC7)") (class "Default")
      (node (ref "IC4") (pin "16") (pinfunction "PC7_16") (pintype "passive"))
      (node (ref "R32") (pin "2") (pinfunction "2_2") (pintype "passive"))
    )
    (net (code "58") (name "Net-(IC4-RESET)") (class "Default")
      (node (ref "IC4") (pin "7") (pinfunction "RESET_7") (pintype "passive"))
      (node (ref "R25") (pin "1") (pinfunction "1_1") (pintype "passive"))
      (node (ref "R27") (pin "1") (pinfunction "1_1") (pintype "passive"))
    )
    (net (code "59") (name "Net-(IC6-REGOUT)") (class "Default")
      (node (ref "C37") (pin "2") (pinfunction "2_2") (pintype "passive"))
      (node (ref "IC6") (pin "10") (pinfunction "REGOUT_10") (pintype "passive"))
    )
    (net (code "60") (name "Net-(J1-CC1)") (class "Default")
      (node (ref "J1") (pin "A5") (pinfunction "CC1_A5") (pintype "bidirectional"))
      (node (ref "R1") (pin "1") (pinfunction "1_1") (pintype "passive"))
    )
    (net (code "61") (name "Net-(J1-CC2)") (class "Default")
      (node (ref "J1") (pin "B5") (pinfunction "CC2_B5") (pintype "bidirectional"))
      (node (ref "R5") (pin "1") (pinfunction "1_1") (pintype "passive"))
    )
    (net (code "62") (name "Net-(J1-DN1)") (class "Default")
      (node (ref "J1") (pin "A7") (pinfunction "DN1_A7") (pintype "bidirectional"))
      (node (ref "J1") (pin "B7") (pinfunction "DN2_B7") (pintype "bidirectional"))
      (node (ref "R7") (pin "1") (pinfunction "1_1") (pintype "passive"))
    )
    (net (code "63") (name "Net-(J1-DP1)") (class "Default")
      (node (ref "J1") (pin "A6") (pinfunction "DP1_A6") (pintype "bidirectional"))
      (node (ref "J1") (pin "B6") (pinfunction "DP2_B6") (pintype "bidirectional"))
      (node (ref "R6") (pin "1") (pinfunction "1_1") (pintype "passive"))
    )
    (net (code "64") (name "Net-(J2-CE)") (class "Default")
      (node (ref "J2") (pin "8") (pinfunction "CE_8") (pintype "passive"))
      (node (ref "R13") (pin "2") (pinfunction "2_2") (pintype "passive"))
    )
    (net (code "65") (name "Net-(J2-~{CHRG})") (class "Default")
      (node (ref "J2") (pin "7") (pinfunction "~{CHRG}_7") (pintype "passive"))
      (node (ref "R14") (pin "2") (pinfunction "2_2") (pintype "passive"))
    )
    (net (code "66") (name "Net-(J2-~{STDBY})") (class "Default")
      (node (ref "J2") (pin "6") (pinfunction "~{STDBY}_6") (pintype "passive"))
      (node (ref "R15") (pin "2") (pinfunction "2_2") (pintype "passive"))
    )
    (net (code "67") (name "Net-(J5-Pad3)") (class "Default")
      (node (ref "J5") (pin "3") (pinfunction "3_3") (pintype "passive"))
      (node (ref "R48") (pin "2") (pinfunction "2_2") (pintype "passive"))
    )
    (net (code "68") (name "Net-(LED1-DIN)") (class "Default")
      (node (ref "LED1") (pin "4") (pinfunction "DIN_4") (pintype "passive"))
      (node (ref "R53") (pin "2") (pinfunction "2_2") (pintype "passive"))
      (node (ref "R56") (pin "1") (pinfunction "1_1") (pintype "passive"))
    )
    (net (code "69") (name "Net-(Q2-D)") (class "Default")
      (node (ref "Q2") (pin "3") (pinfunction "D_3") (pintype "passive"))
      (node (ref "R29") (pin "1") (pinfunction "1_1") (pintype "passive"))
    )
    (net (code "70") (name "Net-(Q2-G)") (class "Default")
      (node (ref "Q2") (pin "1") (pinfunction "G_1") (pintype "passive"))
      (node (ref "R24") (pin "1") (pinfunction "1_1") (pintype "passive"))
      (node (ref "R26") (pin "1") (pinfunction "1_1") (pintype "passive"))
    )
    (net (code "71") (name "Net-(Q3-G)") (class "Default")
      (node (ref "Q3") (pin "1") (pinfunction "G_1") (pintype "passive"))
      (node (ref "R45") (pin "2") (pinfunction "2_2") (pintype "passive"))
      (node (ref "R47") (pin "1") (pinfunction "1_1") (pintype "passive"))
    )
    (net (code "72") (name "Net-(Q4-D)") (class "Default")
      (node (ref "C42") (pin "1") (pinfunction "1_1") (pintype "passive"))
      (node (ref "D8") (pin "1") (pinfunction "1_1") (pintype "passive"))
      (node (ref "Q4") (pin "3") (pinfunction "D_3") (pintype "passive"))
    )
    (net (code "73") (name "Net-(Q4-G)") (class "Default")
      (node (ref "Q4") (pin "1") (pinfunction "G_1") (pintype "passive"))
      (node (ref "R55") (pin "1") (pinfunction "1_1") (pintype "passive"))
      (node (ref "R60") (pin "1") (pinfunction "1_1") (pintype "passive"))
    )
    (net (code "74") (name "Net-(R35-Pad2)") (class "Default")
      (node (ref "R35") (pin "2") (pinfunction "2_2") (pintype "passive"))
      (node (ref "R38") (pin "2") (pinfunction "2_2") (pintype "passive"))
      (node (ref "R41") (pin "1") (pinfunction "1_1") (pintype "passive"))
    )
    (net (code "75") (name "Net-(R36-Pad2)") (class "Default")
      (node (ref "R36") (pin "2") (pinfunction "2_2") (pintype "passive"))
      (node (ref "R39") (pin "2") (pinfunction "2_2") (pintype "passive"))
      (node (ref "R42") (pin "1") (pinfunction "1_1") (pintype "passive"))
    )
    (net (code "76") (name "Net-(R37-Pad2)") (class "Default")
      (node (ref "R37") (pin "2") (pinfunction "2_2") (pintype "passive"))
      (node (ref "R40") (pin "2") (pinfunction "2_2") (pintype "passive"))
      (node (ref "R43") (pin "1") (pinfunction "1_1") (pintype "passive"))
    )
    (net (code "77") (name "Net-(U1-FB)") (class "Default")
      (node (ref "C4") (pin "1") (pinfunction "1_1") (pintype "passive"))
      (node (ref "R8") (pin "1") (pinfunction "1_1") (pintype "passive"))
      (node (ref "R9") (pin "1") (pinfunction "1_1") (pintype "passive"))
      (node (ref "U1") (pin "3") (pinfunction "FB_3") (pintype "passive"))
    )
    (net (code "78") (name "Net-(U1-SW)") (class "Default")
      (node (ref "D2") (pin "1") (pinfunction "1_1") (pintype "passive"))
      (node (ref "L1") (pin "2") (pinfunction "2_2") (pintype "passive"))
      (node (ref "L1") (pin "4") (pinfunction "4_4") (pintype "passive"))
      (node (ref "U1") (pin "1") (pinfunction "SW_1") (pintype "passive"))
    )
    (net (code "79") (name "Net-(U1-~{SHDN})") (class "Default")
      (node (ref "R2") (pin "2") (pinfunction "2_2") (pintype "passive"))
      (node (ref "U1") (pin "4") (pinfunction "~{SHDN}_4") (pintype "passive"))
    )
    (net (code "80") (name "Net-(U2-FB)") (class "Default")
      (node (ref "C5") (pin "1") (pinfunction "1_1") (pintype "passive"))
      (node (ref "R10") (pin "1") (pinfunction "1_1") (pintype "passive"))
      (node (ref "R11") (pin "1") (pinfunction "1_1") (pintype "passive"))
      (node (ref "U2") (pin "3") (pinfunction "FB_3") (pintype "passive"))
    )
    (net (code "81") (name "Net-(U2-SW)") (class "Default")
      (node (ref "D3") (pin "1") (pinfunction "1_1") (pintype "passive"))
      (node (ref "L2") (pin "2") (pinfunction "2_2") (pintype "passive"))
      (node (ref "L2") (pin "4") (pinfunction "4_4") (pintype "passive"))
      (node (ref "U2") (pin "1") (pinfunction "SW_1") (pintype "passive"))
    )
    (net (code "82") (name "Net-(U2-~{SHDN})") (class "Default")
      (node (ref "R3") (pin "2") (pinfunction "2_2") (pintype "passive"))
      (node (ref "U2") (pin "4") (pinfunction "~{SHDN}_4") (pintype "passive"))
    )
    (net (code "83") (name "OSC_IN") (class "Default")
      (node (ref "B1") (pin "5") (pinfunction "PH0-OSC_IN_5") (pintype "passive"))
      (node (ref "C16") (pin "2") (pinfunction "2_2") (pintype "passive"))
      (node (ref "R18") (pin "2") (pinfunction "2_2") (pintype "passive"))
      (node (ref "Y1") (pin "2") (pinfunction "2_2") (pintype "passive"))
    )
    (net (code "84") (name "OSC_OUT") (class "Default")
      (node (ref "B1") (pin "6") (pinfunction "PH1-OSC_OUT_6") (pintype "passive"))
      (node (ref "C12") (pin "2") (pinfunction "2_2") (pintype "passive"))
      (node (ref "R18") (pin "1") (pinfunction "1_1") (pintype "passive"))
      (node (ref "Y1") (pin "1") (pinfunction "1_1") (pintype "passive"))
    )
    (net (code "85") (name "SWCLK") (class "Default")
      (node (ref "B1") (pin "49") (pinfunction "PA14_49") (pintype "passive"))
      (node (ref "R20") (pin "2") (pinfunction "2_2") (pintype "passive"))
    )
    (net (code "86") (name "SWDIO") (class "Default")
      (node (ref "B1") (pin "46") (pinfunction "PA13_46") (pintype "passive"))
      (node (ref "R21") (pin "2") (pinfunction "2_2") (pintype "passive"))
    )
    (net (code "87") (name "TENZO_RX") (class "Default")
      (node (ref "B1") (pin "54") (pinfunction "PD2_54") (pintype "passive"))
      (node (ref "R49") (pin "2") (pinfunction "2_2") (pintype "passive"))
    )
    (net (code "88") (name "TENZO_TX") (class "Default")
      (node (ref "B1") (pin "53") (pinfunction "PC12_53") (pintype "passive"))
      (node (ref "R50") (pin "2") (pinfunction "2_2") (pintype "passive"))
    )
    (net (code "89") (name "TEST1") (class "Default")
      (node (ref "B1") (pin "40") (pinfunction "PC9_40") (pintype "passive"))
      (node (ref "TP1") (pin "1") (pinfunction "1_1") (pintype "passive"))
    )
    (net (code "90") (name "TRM_ON") (class "Default")
      (node (ref "B1") (pin "33") (pinfunction "PB12_33") (pintype "passive"))
      (node (ref "R47") (pin "2") (pinfunction "2_2") (pintype "passive"))
    )
    (net (code "91") (name "TRM_SCL") (class "Default")
      (node (ref "B1") (pin "58") (pinfunction "PB6_58") (pintype "passive"))
      (node (ref "IC5") (pin "1") (pinfunction "SCL_1") (pintype "passive"))
      (node (ref "R44") (pin "1") (pinfunction "1_1") (pintype "passive"))
    )
    (net (code "92") (name "TRM_SDA") (class "Default")
      (node (ref "B1") (pin "59") (pinfunction "PB7_59") (pintype "passive"))
      (node (ref "IC5") (pin "6") (pinfunction "SDA_6") (pintype "passive"))
      (node (ref "R46") (pin "2") (pinfunction "2_2") (pintype "passive"))
    )
    (net (code "93") (name "USB_N") (class "Default")
      (node (ref "B1") (pin "44") (pinfunction "PA11_44") (pintype "passive"))
      (node (ref "IC1") (pin "1") (pinfunction "I/O1_1_1") (pintype "passive"))
      (node (ref "IC1") (pin "6") (pinfunction "I/O1_2_6") (pintype "passive"))
      (node (ref "R7") (pin "2") (pinfunction "2_2") (pintype "passive"))
    )
    (net (code "94") (name "USB_P") (class "Default")
      (node (ref "B1") (pin "45") (pinfunction "PA12_45") (pintype "passive"))
      (node (ref "IC1") (pin "3") (pinfunction "I/O2_1_3") (pintype "passive"))
      (node (ref "IC1") (pin "4") (pinfunction "I/O2_2_4") (pintype "passive"))
      (node (ref "R4") (pin "1") (pinfunction "1_1") (pintype "passive"))
      (node (ref "R6") (pin "2") (pinfunction "2_2") (pintype "passive"))
    )
    (net (code "95") (name "VBUS") (class "Default")
      (node (ref "IC1") (pin "5") (pinfunction "VBUS_5") (pintype "passive"))
      (node (ref "J1") (pin "A4_B9") (pinfunction "VBUS_A4_B9") (pintype "power_in"))
      (node (ref "J1") (pin "B4_A9") (pinfunction "VBUS_B4_A9") (pintype "power_in"))
      (node (ref "J3") (pin "8") (pinfunction "8_8") (pintype "passive"))
      (node (ref "R12") (pin "1") (pinfunction "1_1") (pintype "passive"))
    )
    (net (code "96") (name "VBUS_V") (class "Default")
      (node (ref "J2") (pin "4") (pinfunction "VCC4_4") (pintype "passive"))
      (node (ref "R12") (pin "2") (pinfunction "2_2") (pintype "passive"))
      (node (ref "R13") (pin "1") (pinfunction "1_1") (pintype "passive"))
      (node (ref "R14") (pin "1") (pinfunction "1_1") (pintype "passive"))
      (node (ref "R15") (pin "1") (pinfunction "1_1") (pintype "passive"))
      (node (ref "R43") (pin "2") (pinfunction "2_2") (pintype "passive"))
    )
    (net (code "97") (name "VCAP1") (class "Default")
      (node (ref "B1") (pin "30") (pinfunction "VCAP_1_30") (pintype "passive"))
      (node (ref "C15") (pin "1") (pinfunction "1_1") (pintype "passive"))
    )
    (net (code "98") (name "V_BAT") (class "Default")
      (node (ref "C13") (pin "2") (pinfunction "2_2") (pintype "passive"))
      (node (ref "C14") (pin "1") (pinfunction "1_1") (pintype "passive"))
      (node (ref "C2") (pin "2") (pinfunction "2_2") (pintype "passive"))
      (node (ref "C3") (pin "2") (pinfunction "2_2") (pintype "passive"))
      (node (ref "J2") (pin "5") (pinfunction "BAT_5") (pintype "passive"))
      (node (ref "L1") (pin "1") (pinfunction "1_1") (pintype "passive"))
      (node (ref "L1") (pin "3") (pinfunction "3_3") (pintype "passive"))
      (node (ref "L2") (pin "1") (pinfunction "1_1") (pintype "passive"))
      (node (ref "L2") (pin "3") (pinfunction "3_3") (pintype "passive"))
      (node (ref "R2") (pin "1") (pinfunction "1_1") (pintype "passive"))
      (node (ref "R28") (pin "2") (pinfunction "2_2") (pintype "passive"))
      (node (ref "R3") (pin "1") (pinfunction "1_1") (pintype "passive"))
      (node (ref "R41") (pin "2") (pinfunction "2_2") (pintype "passive"))
      (node (ref "U1") (pin "5") (pinfunction "VIN_5") (pintype "passive"))
      (node (ref "U2") (pin "5") (pinfunction "VIN_5") (pintype "passive"))
    )
    (net (code "99") (name "V_BAT-") (class "Default")
      (node (ref "C18") (pin "2") (pinfunction "2_2") (pintype "passive"))
      (node (ref "IC3") (pin "6") (pinfunction "GND_6") (pintype "passive"))
      (node (ref "Q1") (pin "1") (pinfunction "S1_1") (pintype "passive"))
    )
    (net (code "100") (name "V_GYDRO") (class "Default")
      (node (ref "C4") (pin "2") (pinfunction "2_2") (pintype "passive"))
      (node (ref "C6") (pin "1") (pinfunction "1_1") (pintype "passive"))
      (node (ref "C9") (pin "2") (pinfunction "2_2") (pintype "passive"))
      (node (ref "D2") (pin "2") (pinfunction "2_2") (pintype "passive"))
      (node (ref "J4") (pin "1") (pinfunction "1_1") (pintype "passive"))
      (node (ref "J4") (pin "2") (pinfunction "2_2") (pintype "passive"))
      (node (ref "R8") (pin "2") (pinfunction "2_2") (pintype "passive"))
    )
    (net (code "101") (name "unconnected-(B1-PA1-Pad15)") (class "Default")
      (node (ref "B1") (pin "15") (pinfunction "PA1_15") (pintype "passive"))
    )
    (net (code "102") (name "unconnected-(B1-PA2-Pad16)") (class "Default")
      (node (ref "B1") (pin "16") (pinfunction "PA2_16") (pintype "passive"))
    )
    (net (code "103") (name "unconnected-(B1-PA3-Pad17)") (class "Default")
      (node (ref "B1") (pin "17") (pinfunction "PA3_17") (pintype "passive"))
    )
    (net (code "104") (name "unconnected-(B1-PA8-Pad41)") (class "Default")
      (node (ref "B1") (pin "41") (pinfunction "PA8_41") (pintype "passive"))
    )
    (net (code "105") (name "unconnected-(B1-PA10-Pad43)") (class "Default")
      (node (ref "B1") (pin "43") (pinfunction "PA10_43") (pintype "passive"))
    )
    (net (code "106") (name "unconnected-(B1-PB1-Pad27)") (class "Default")
      (node (ref "B1") (pin "27") (pinfunction "PB1_27") (pintype "passive"))
    )
    (net (code "107") (name "unconnected-(B1-PB2-Pad28)") (class "Default")
      (node (ref "B1") (pin "28") (pinfunction "PB2_28") (pintype "passive"))
    )
    (net (code "108") (name "unconnected-(B1-PB8-Pad61)") (class "Default")
      (node (ref "B1") (pin "61") (pinfunction "PB8_61") (pintype "passive"))
    )
    (net (code "109") (name "unconnected-(B1-PB10-Pad29)") (class "Default")
      (node (ref "B1") (pin "29") (pinfunction "PB10_29") (pintype "passive"))
    )
    (net (code "110") (name "unconnected-(B1-PC13-Pad2)") (class "Default")
      (node (ref "B1") (pin "2") (pinfunction "PC13_2") (pintype "passive"))
    )
    (net (code "111") (name "unconnected-(B1-PC14-OSC32_IN-Pad3)") (class "Default")
      (node (ref "B1") (pin "3") (pinfunction "PC14-OSC32_IN_3") (pintype "passive"))
    )
    (net (code "112") (name "unconnected-(B1-VBAT-Pad1)") (class "Default")
      (node (ref "B1") (pin "1") (pinfunction "VBAT_1") (pintype "passive"))
    )
    (net (code "113") (name "unconnected-(B2-EP-Pad17)") (class "Default")
      (node (ref "B2") (pin "17") (pinfunction "EP_17") (pintype "passive"))
    )
    (net (code "114") (name "unconnected-(B2-NC_1-Pad5)") (class "Default")
      (node (ref "B2") (pin "5") (pinfunction "NC_1_5") (pintype "passive"))
    )
    (net (code "115") (name "unconnected-(B2-NC_2-Pad6)") (class "Default")
      (node (ref "B2") (pin "6") (pinfunction "NC_2_6") (pintype "passive"))
    )
    (net (code "116") (name "unconnected-(B2-NC_3-Pad7)") (class "Default")
      (node (ref "B2") (pin "7") (pinfunction "NC_3_7") (pintype "passive"))
    )
    (net (code "117") (name "unconnected-(B2-NC_4-Pad8)") (class "Default")
      (node (ref "B2") (pin "8") (pinfunction "NC_4_8") (pintype "passive"))
    )
    (net (code "118") (name "unconnected-(B2-NC_5-Pad16)") (class "Default")
      (node (ref "B2") (pin "16") (pinfunction "NC_5_16") (pintype "passive"))
    )
    (net (code "119") (name "unconnected-(B2-~{INT}-Pad15)") (class "Default")
      (node (ref "B2") (pin "15") (pinfunction "~{INT}_15") (pintype "passive"))
    )
    (net (code "120") (name "unconnected-(IC3-TD-Pad4)") (class "Default")
      (node (ref "IC3") (pin "4") (pinfunction "TD_4") (pintype "passive"))
    )
    (net (code "121") (name "unconnected-(IC4-ANT-Pad29)") (class "Default")
      (node (ref "IC4") (pin "29") (pinfunction "ANT_29") (pintype "passive"))
    )
    (net (code "122") (name "unconnected-(IC4-AOUT_N-Pad6)") (class "Default")
      (node (ref "IC4") (pin "6") (pinfunction "AOUT_N_6") (pintype "passive"))
    )
    (net (code "123") (name "unconnected-(IC4-AOUT_P-Pad5)") (class "Default")
      (node (ref "IC4") (pin "5") (pinfunction "AOUT_P_5") (pintype "passive"))
    )
    (net (code "124") (name "unconnected-(IC4-LED-Pad27)") (class "Default")
      (node (ref "IC4") (pin "27") (pinfunction "LED_27") (pintype "passive"))
    )
    (net (code "125") (name "unconnected-(IC4-MIC_BIAS-Pad2)") (class "Default")
      (node (ref "IC4") (pin "2") (pinfunction "MIC_BIAS_2") (pintype "passive"))
    )
    (net (code "126") (name "unconnected-(IC4-MIC_IN-Pad3)") (class "Default")
      (node (ref "IC4") (pin "3") (pinfunction "MIC_IN_3") (pintype "passive"))
    )
    (net (code "127") (name "unconnected-(IC4-PA0-Pad22)") (class "Default")
      (node (ref "IC4") (pin "22") (pinfunction "PA0_22") (pintype "passive"))
    )
    (net (code "128") (name "unconnected-(IC4-PA1-Pad21)") (class "Default")
      (node (ref "IC4") (pin "21") (pinfunction "PA1_21") (pintype "passive"))
    )
    (net (code "129") (name "unconnected-(IC4-PA2-Pad20)") (class "Default")
      (node (ref "IC4") (pin "20") (pinfunction "PA2_20") (pintype "passive"))
    )
    (net (code "130") (name "unconnected-(IC4-PA3-Pad19)") (class "Default")
      (node (ref "IC4") (pin "19") (pinfunction "PA3_19") (pintype "passive"))
    )
    (net (code "131") (name "unconnected-(IC4-PA5-Pad26)") (class "Default")
      (node (ref "IC4") (pin "26") (pinfunction "PA5_26") (pintype "passive"))
    )
    (net (code "132") (name "unconnected-(IC4-PD4-Pad15)") (class "Default")
      (node (ref "IC4") (pin "15") (pinfunction "PD4_15") (pintype "passive"))
    )
    (net (code "133") (name "unconnected-(IC4-PD5-Pad14)") (class "Default")
      (node (ref "IC4") (pin "14") (pinfunction "PD5_14") (pintype "passive"))
    )
    (net (code "134") (name "unconnected-(IC4-PD6-Pad13)") (class "Default")
      (node (ref "IC4") (pin "13") (pinfunction "PD6_13") (pintype "passive"))
    )
    (net (code "135") (name "unconnected-(IC4-PD7-Pad12)") (class "Default")
      (node (ref "IC4") (pin "12") (pinfunction "PD7_12") (pintype "passive"))
    )
    (net (code "136") (name "unconnected-(IC4-VCHG-Pad8)") (class "Default")
      (node (ref "IC4") (pin "8") (pinfunction "VCHG_8") (pintype "passive"))
    )
    (net (code "137") (name "unconnected-(IC4-VDDIO-Pad11)") (class "Default")
      (node (ref "IC4") (pin "11") (pinfunction "VDDIO_11") (pintype "passive"))
    )
    (net (code "138") (name "unconnected-(IC4-VMID-Pad4)") (class "Default")
      (node (ref "IC4") (pin "4") (pinfunction "VMID_4") (pintype "passive"))
    )
    (net (code "139") (name "unconnected-(IC5-ALERT-Pad3)") (class "Default")
      (node (ref "IC5") (pin "3") (pinfunction "ALERT_3") (pintype "passive"))
    )
    (net (code "140") (name "unconnected-(IC6-AUX_CL-Pad7)") (class "Default")
      (node (ref "IC6") (pin "7") (pinfunction "AUX_CL_7") (pintype "passive"))
    )
    (net (code "141") (name "unconnected-(IC6-AUX_DA-Pad21)") (class "Default")
      (node (ref "IC6") (pin "21") (pinfunction "AUX_DA_21") (pintype "passive"))
    )
    (net (code "142") (name "unconnected-(IC6-EP-Pad25)") (class "Default")
      (node (ref "IC6") (pin "25") (pinfunction "EP_25") (pintype "passive"))
    )
    (net (code "143") (name "unconnected-(IC6-FSYNC-Pad11)") (class "Default")
      (node (ref "IC6") (pin "11") (pinfunction "FSYNC_11") (pintype "passive"))
    )
    (net (code "144") (name "unconnected-(IC6-INT-Pad12)") (class "Default")
      (node (ref "IC6") (pin "12") (pinfunction "INT_12") (pintype "passive"))
    )
    (net (code "145") (name "unconnected-(IC6-NC_1-Pad2)") (class "Default")
      (node (ref "IC6") (pin "2") (pinfunction "NC_1_2") (pintype "passive"))
    )
    (net (code "146") (name "unconnected-(IC6-NC_2-Pad3)") (class "Default")
      (node (ref "IC6") (pin "3") (pinfunction "NC_2_3") (pintype "passive"))
    )
    (net (code "147") (name "unconnected-(IC6-NC_3-Pad4)") (class "Default")
      (node (ref "IC6") (pin "4") (pinfunction "NC_3_4") (pintype "passive"))
    )
    (net (code "148") (name "unconnected-(IC6-NC_4-Pad5)") (class "Default")
      (node (ref "IC6") (pin "5") (pinfunction "NC_4_5") (pintype "passive"))
    )
    (net (code "149") (name "unconnected-(IC6-NC_5-Pad6)") (class "Default")
      (node (ref "IC6") (pin "6") (pinfunction "NC_5_6") (pintype "passive"))
    )
    (net (code "150") (name "unconnected-(IC6-NC_6-Pad14)") (class "Default")
      (node (ref "IC6") (pin "14") (pinfunction "NC_6_14") (pintype "passive"))
    )
    (net (code "151") (name "unconnected-(IC6-NC_7-Pad15)") (class "Default")
      (node (ref "IC6") (pin "15") (pinfunction "NC_7_15") (pintype "passive"))
    )
    (net (code "152") (name "unconnected-(IC6-NC_8-Pad16)") (class "Default")
      (node (ref "IC6") (pin "16") (pinfunction "NC_8_16") (pintype "passive"))
    )
    (net (code "153") (name "unconnected-(IC6-NC_9-Pad17)") (class "Default")
      (node (ref "IC6") (pin "17") (pinfunction "NC_9_17") (pintype "passive"))
    )
    (net (code "154") (name "unconnected-(IC6-RESV_2-Pad19)") (class "Default")
      (node (ref "IC6") (pin "19") (pinfunction "RESV_2_19") (pintype "passive"))
    )
    (net (code "155") (name "unconnected-(J1-SBU1-PadA8)") (class "Default")
      (node (ref "J1") (pin "A8") (pinfunction "SBU1_A8") (pintype "bidirectional"))
    )
    (net (code "156") (name "unconnected-(J1-SBU2-PadB8)") (class "Default")
      (node (ref "J1") (pin "B8") (pinfunction "SBU2_B8") (pintype "bidirectional"))
    )
    (net (code "157") (name "unconnected-(J3-Pad1)") (class "Default")
      (node (ref "J3") (pin "1") (pinfunction "1_1") (pintype "passive"))
    )
    (net (code "158") (name "unconnected-(J3-Pad2)") (class "Default")
      (node (ref "J3") (pin "2") (pinfunction "2_2") (pintype "passive"))
    )
    (net (code "159") (name "unconnected-(J3-Pad10)") (class "Default")
      (node (ref "J3") (pin "10") (pinfunction "10_10") (pintype "passive"))
    )
    (net (code "160") (name "unconnected-(J3-Pad11)") (class "Default")
      (node (ref "J3") (pin "11") (pinfunction "11_11") (pintype "passive"))
    )
    (net (code "161") (name "unconnected-(J3-Pad12)") (class "Default")
      (node (ref "J3") (pin "12") (pinfunction "12_12") (pintype "passive"))
    )
    (net (code "162") (name "unconnected-(J4-Pad6)") (class "Default")
      (node (ref "J4") (pin "6") (pinfunction "6_6") (pintype "passive"))
    )
    (net (code "163") (name "unconnected-(LED1-DOUT-Pad2)") (class "Default")
      (node (ref "LED1") (pin "2") (pinfunction "DOUT_2") (pintype "passive"))
    )
    (net (code "164") (name "unconnected-(Q1-D1{slash}D2_1-Pad2)") (class "Default")
      (node (ref "Q1") (pin "2") (pinfunction "D1/D2_1_2") (pintype "passive"))
    )
    (net (code "165") (name "unconnected-(Q1-D1{slash}D2_2-Pad5)") (class "Default")
      (node (ref "Q1") (pin "5") (pinfunction "D1/D2_2_5") (pintype "passive"))
    )
  )
)
